# PX4uNode_V0_1_1.net
KiCad netlist of a schematic drawn in EAGLE
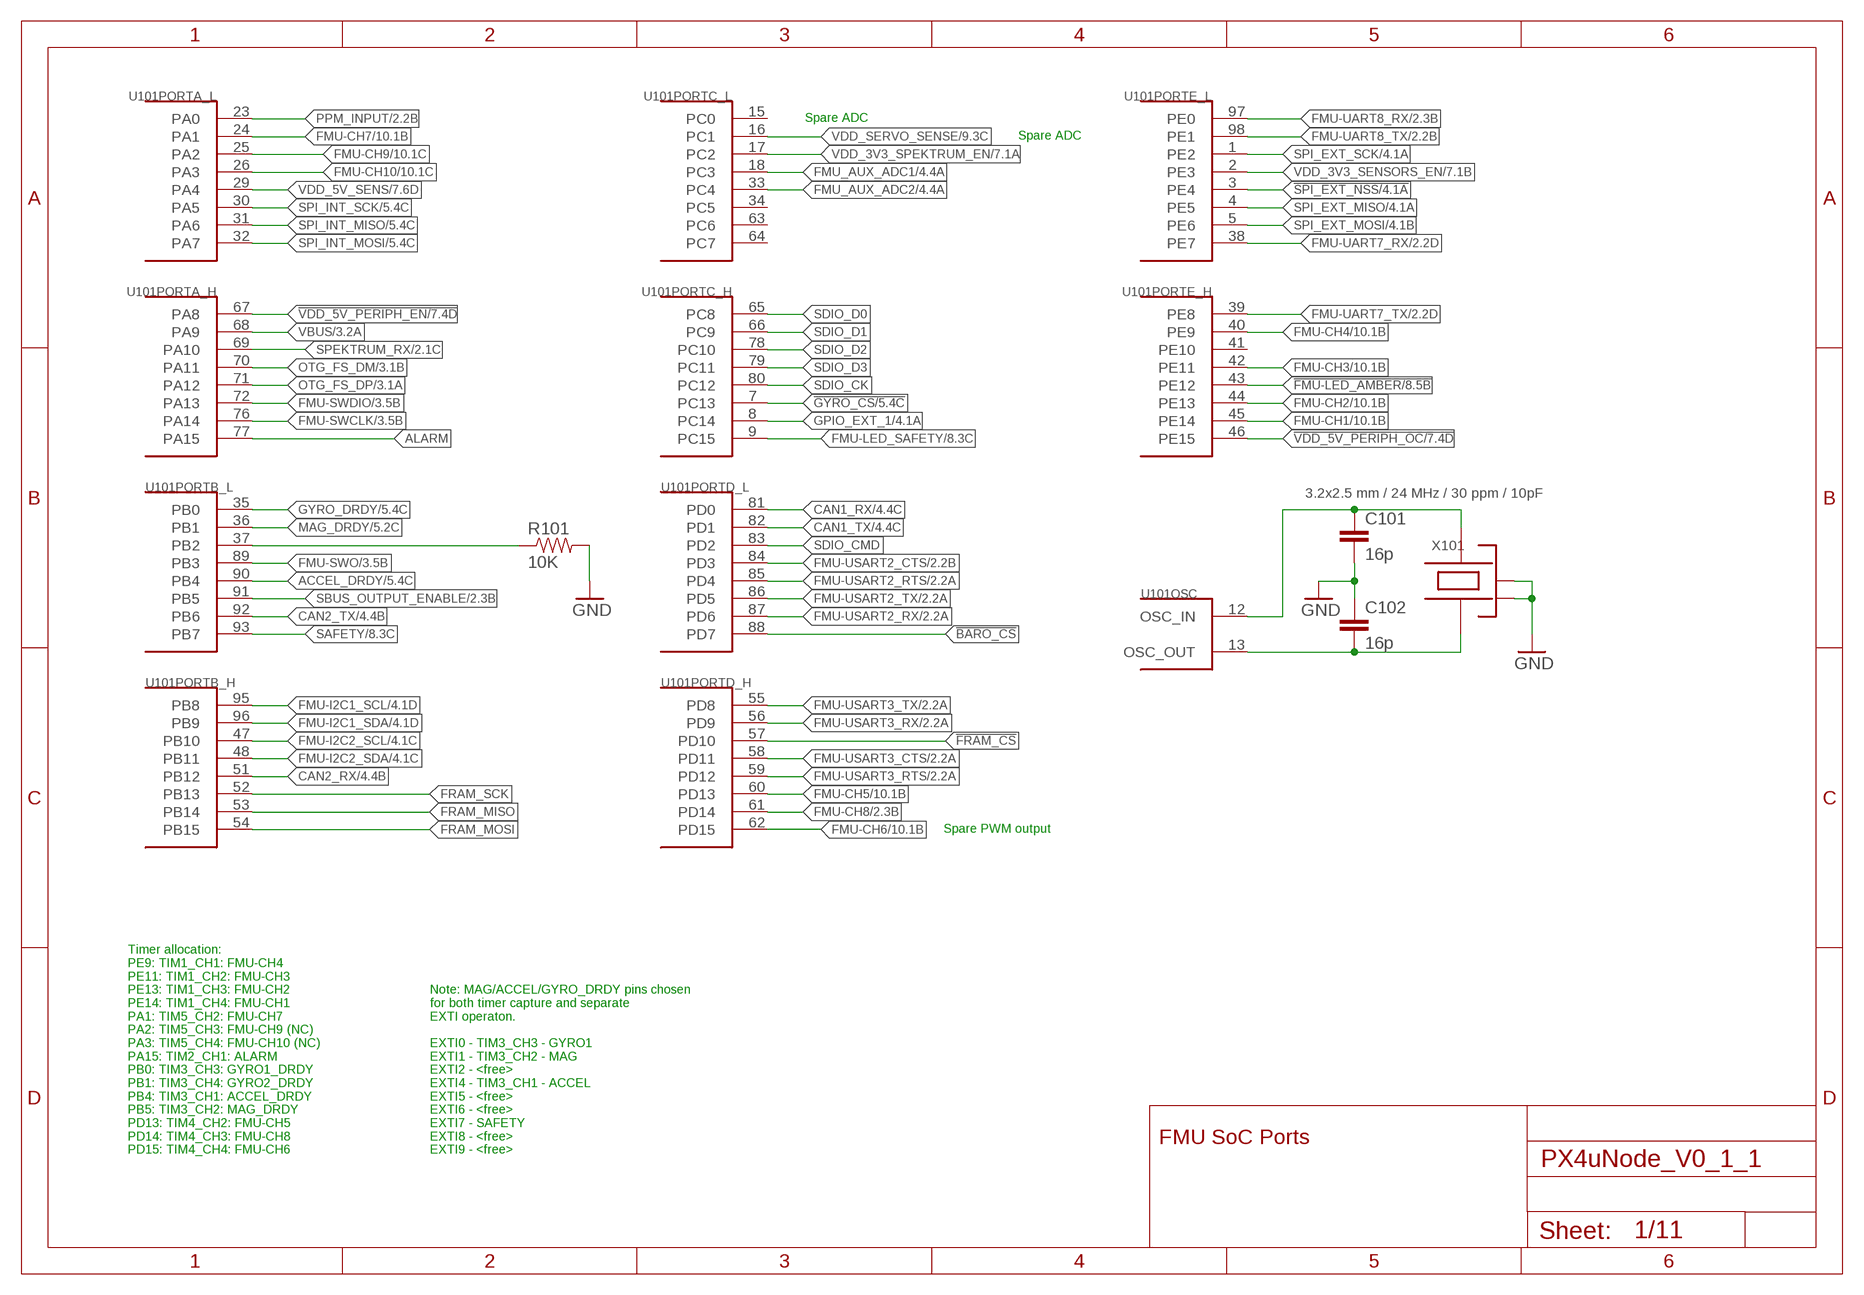
[diagram p0: schematic, sheet 1]
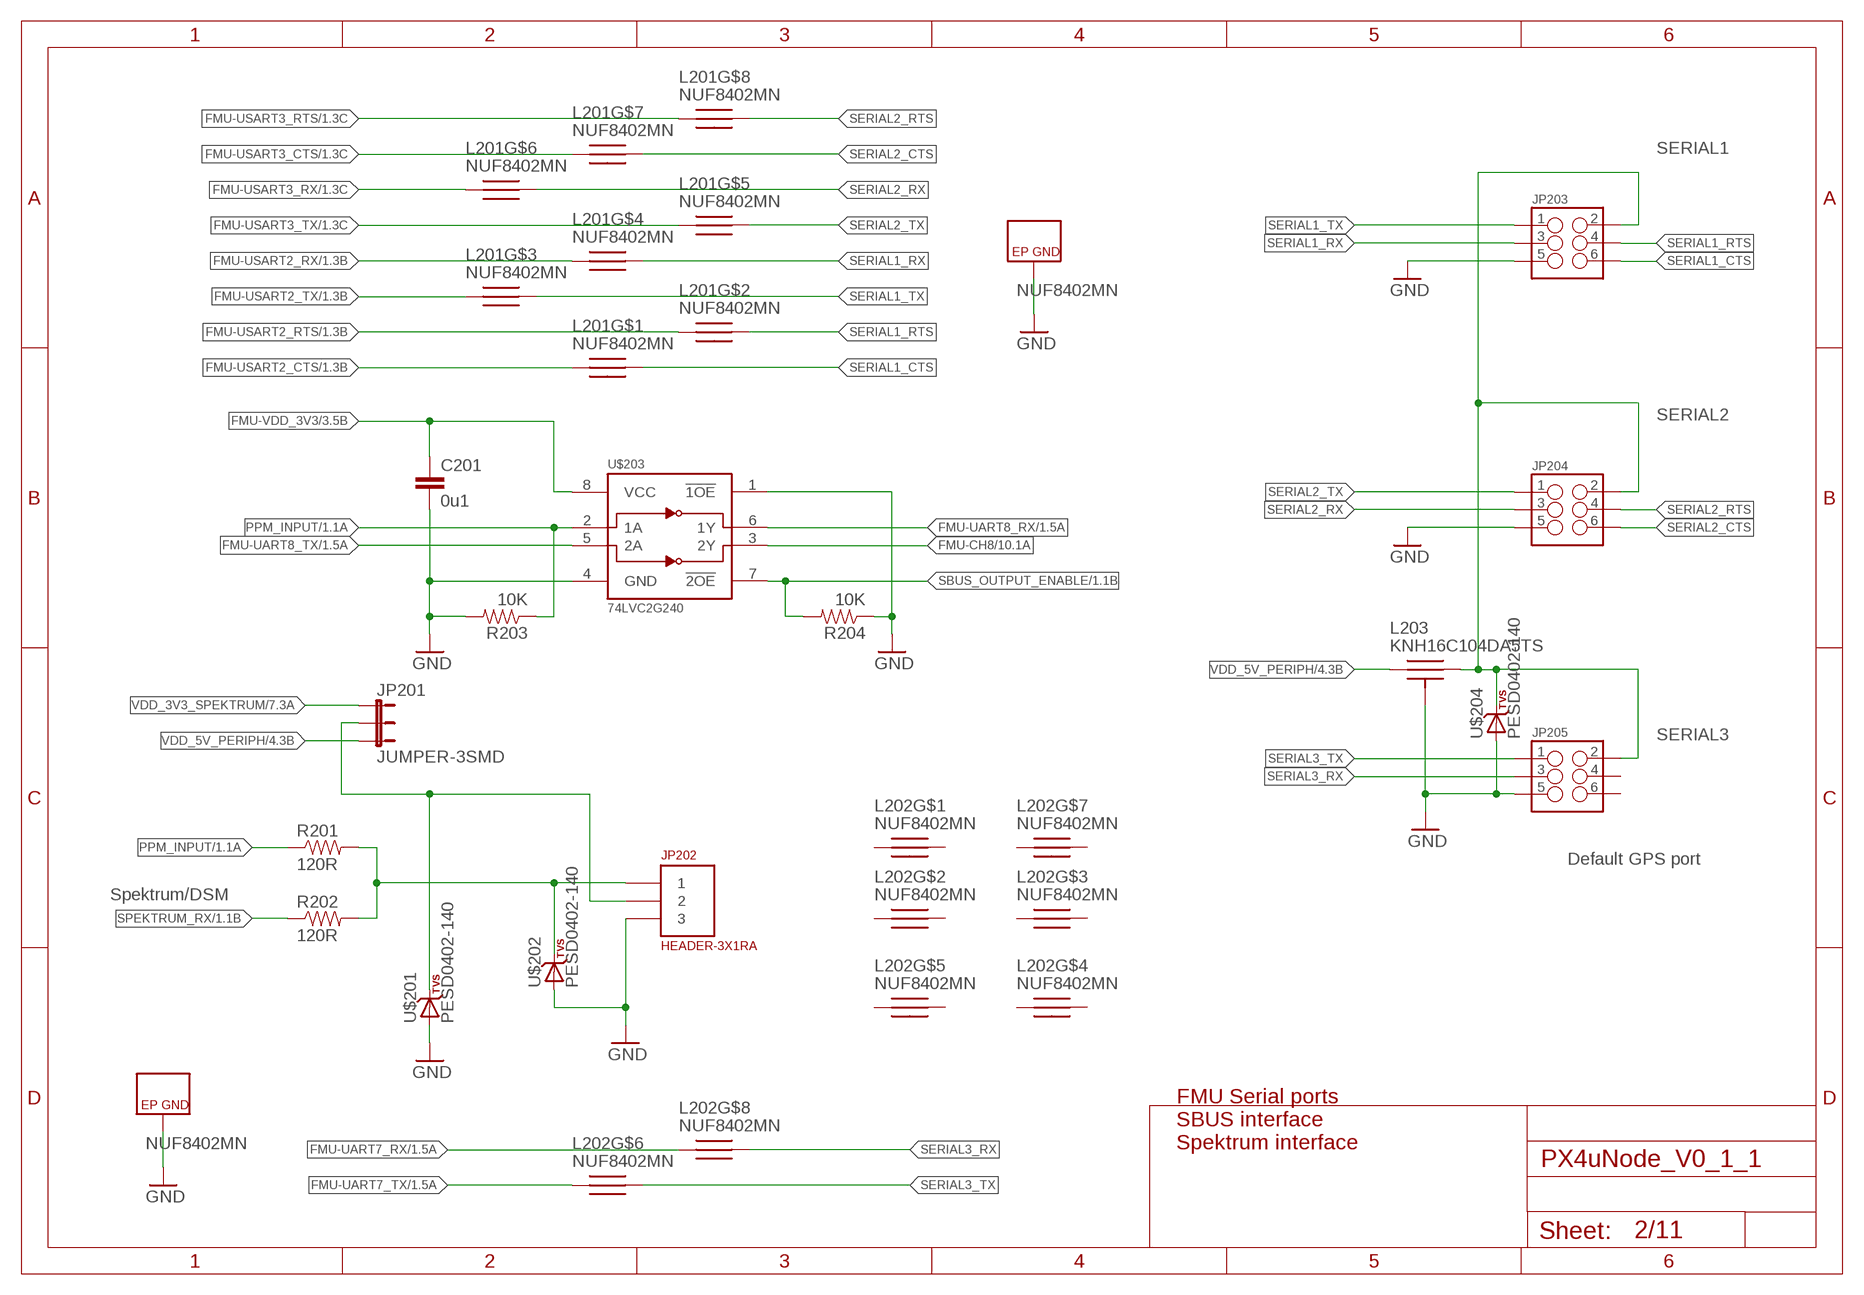
[diagram p1: schematic, sheet 2]
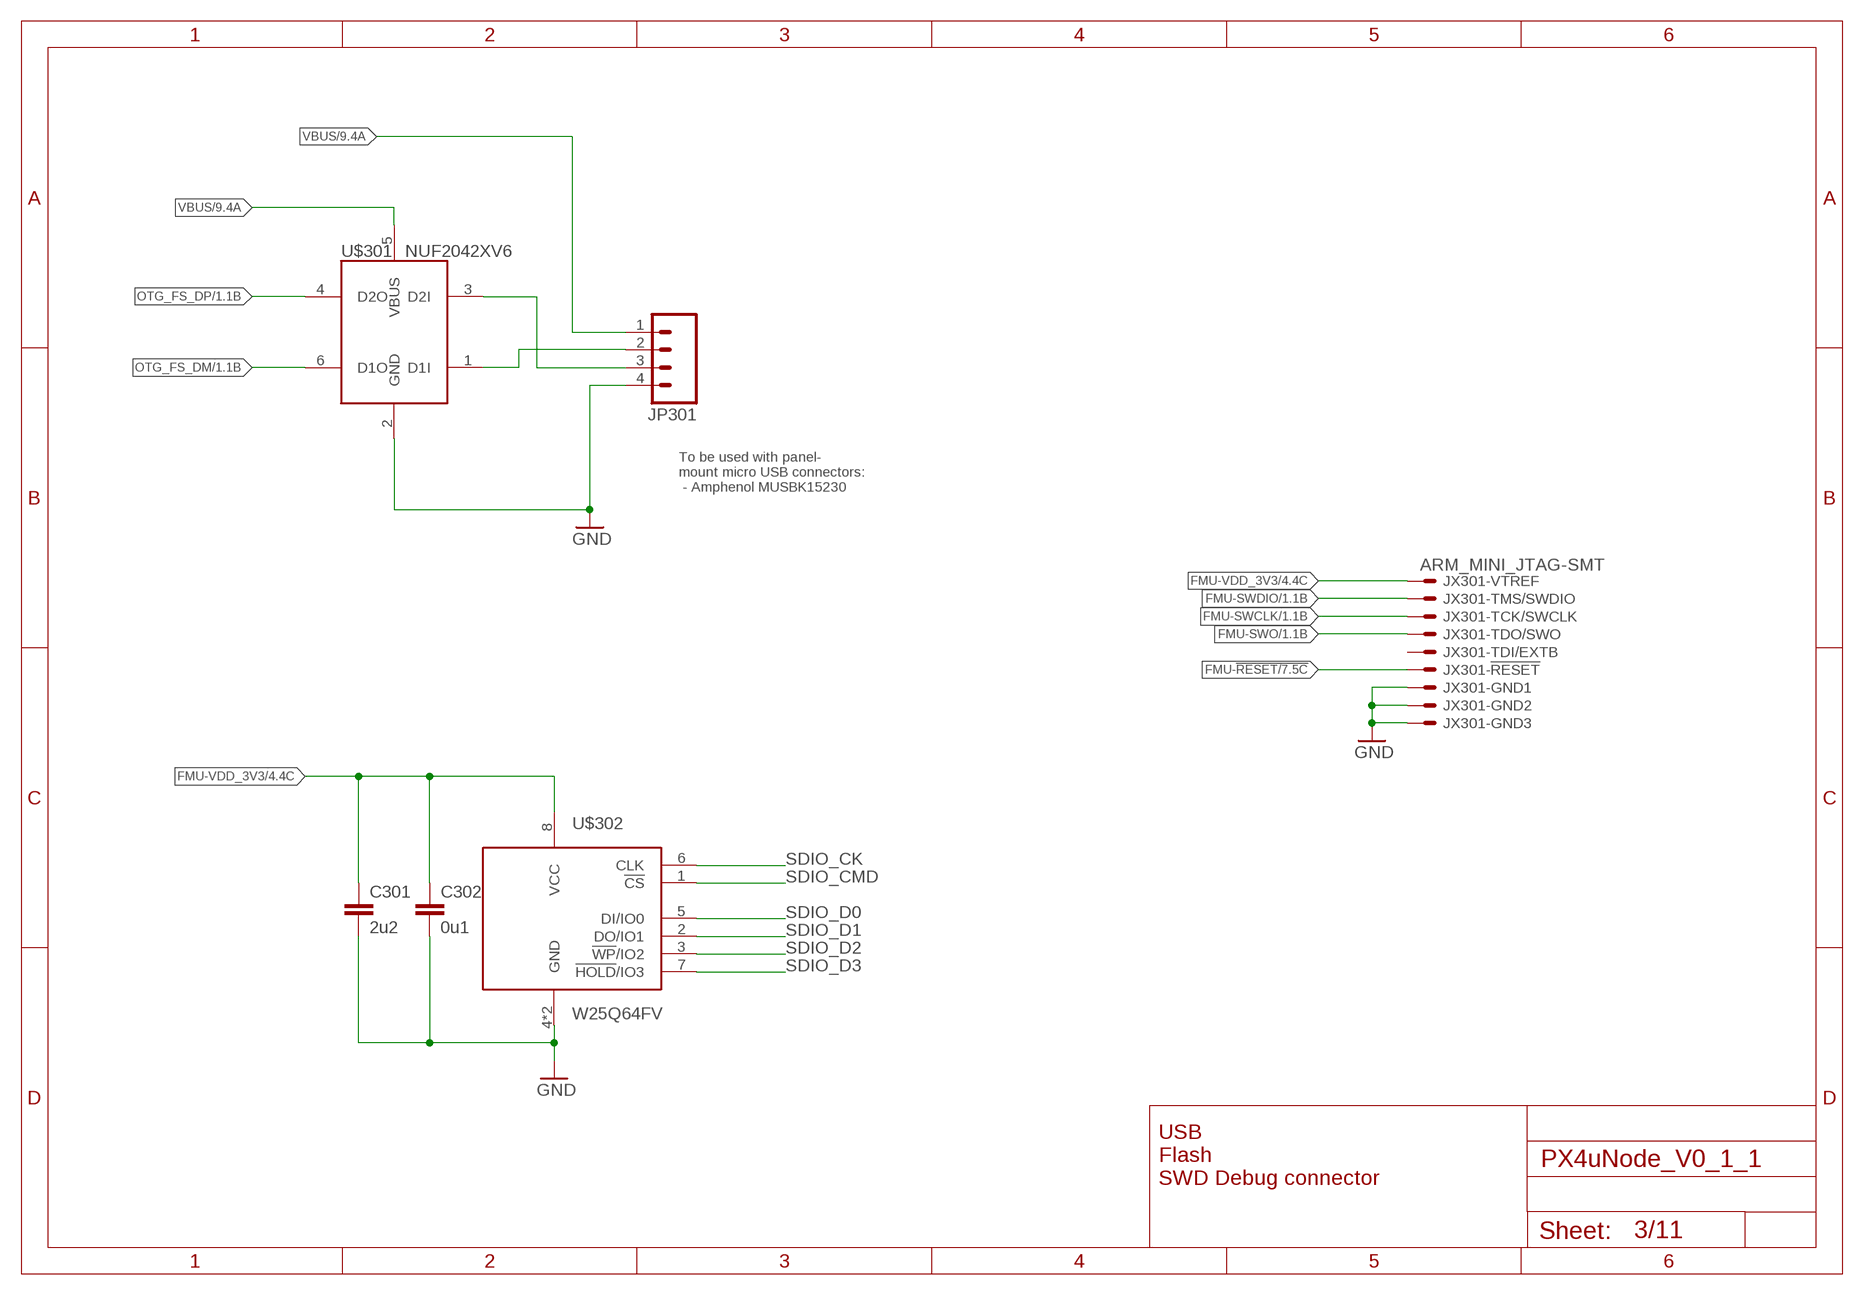
[diagram p2: schematic, sheet 3]
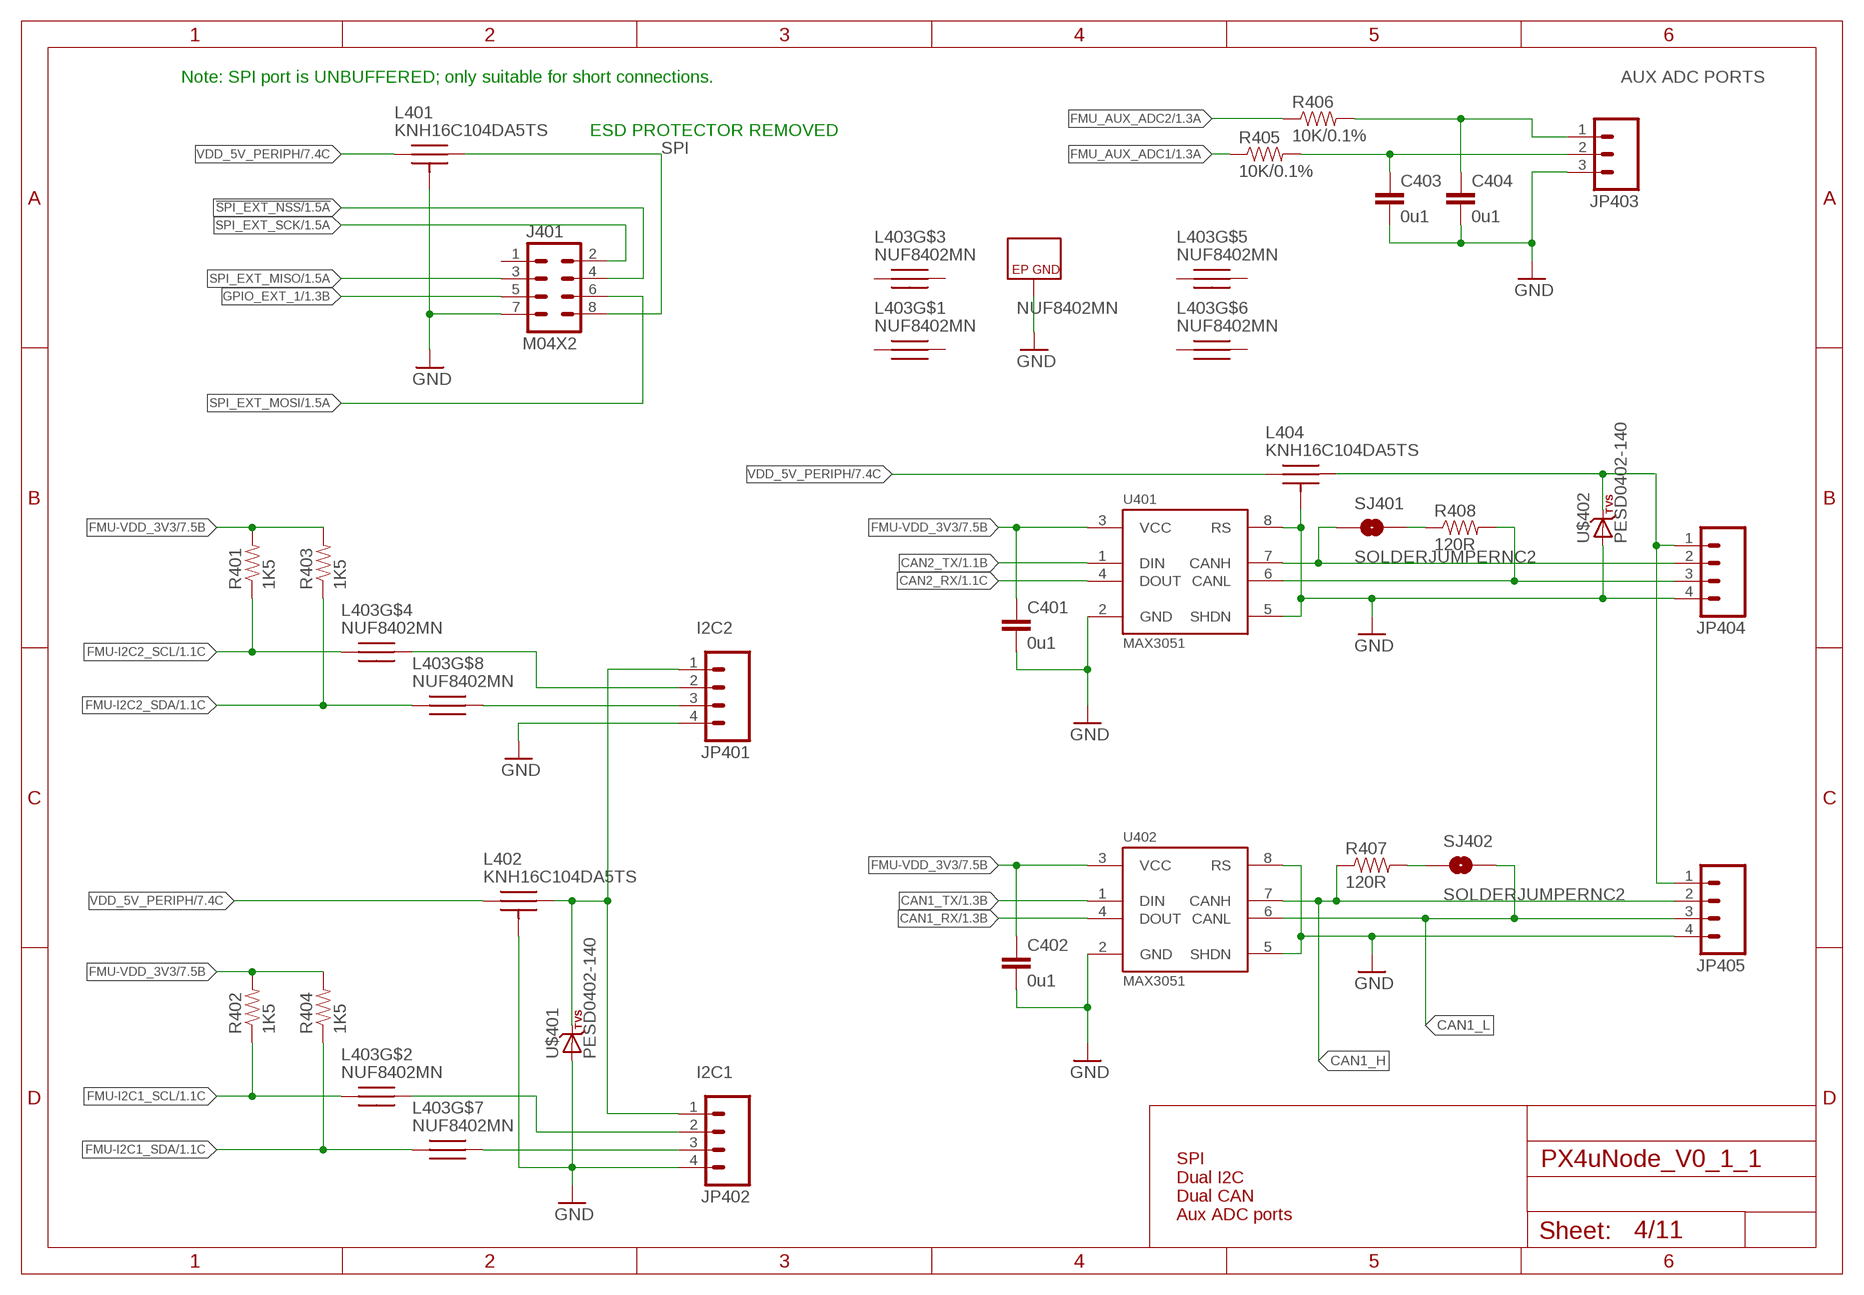
[diagram p3: schematic, sheet 4]
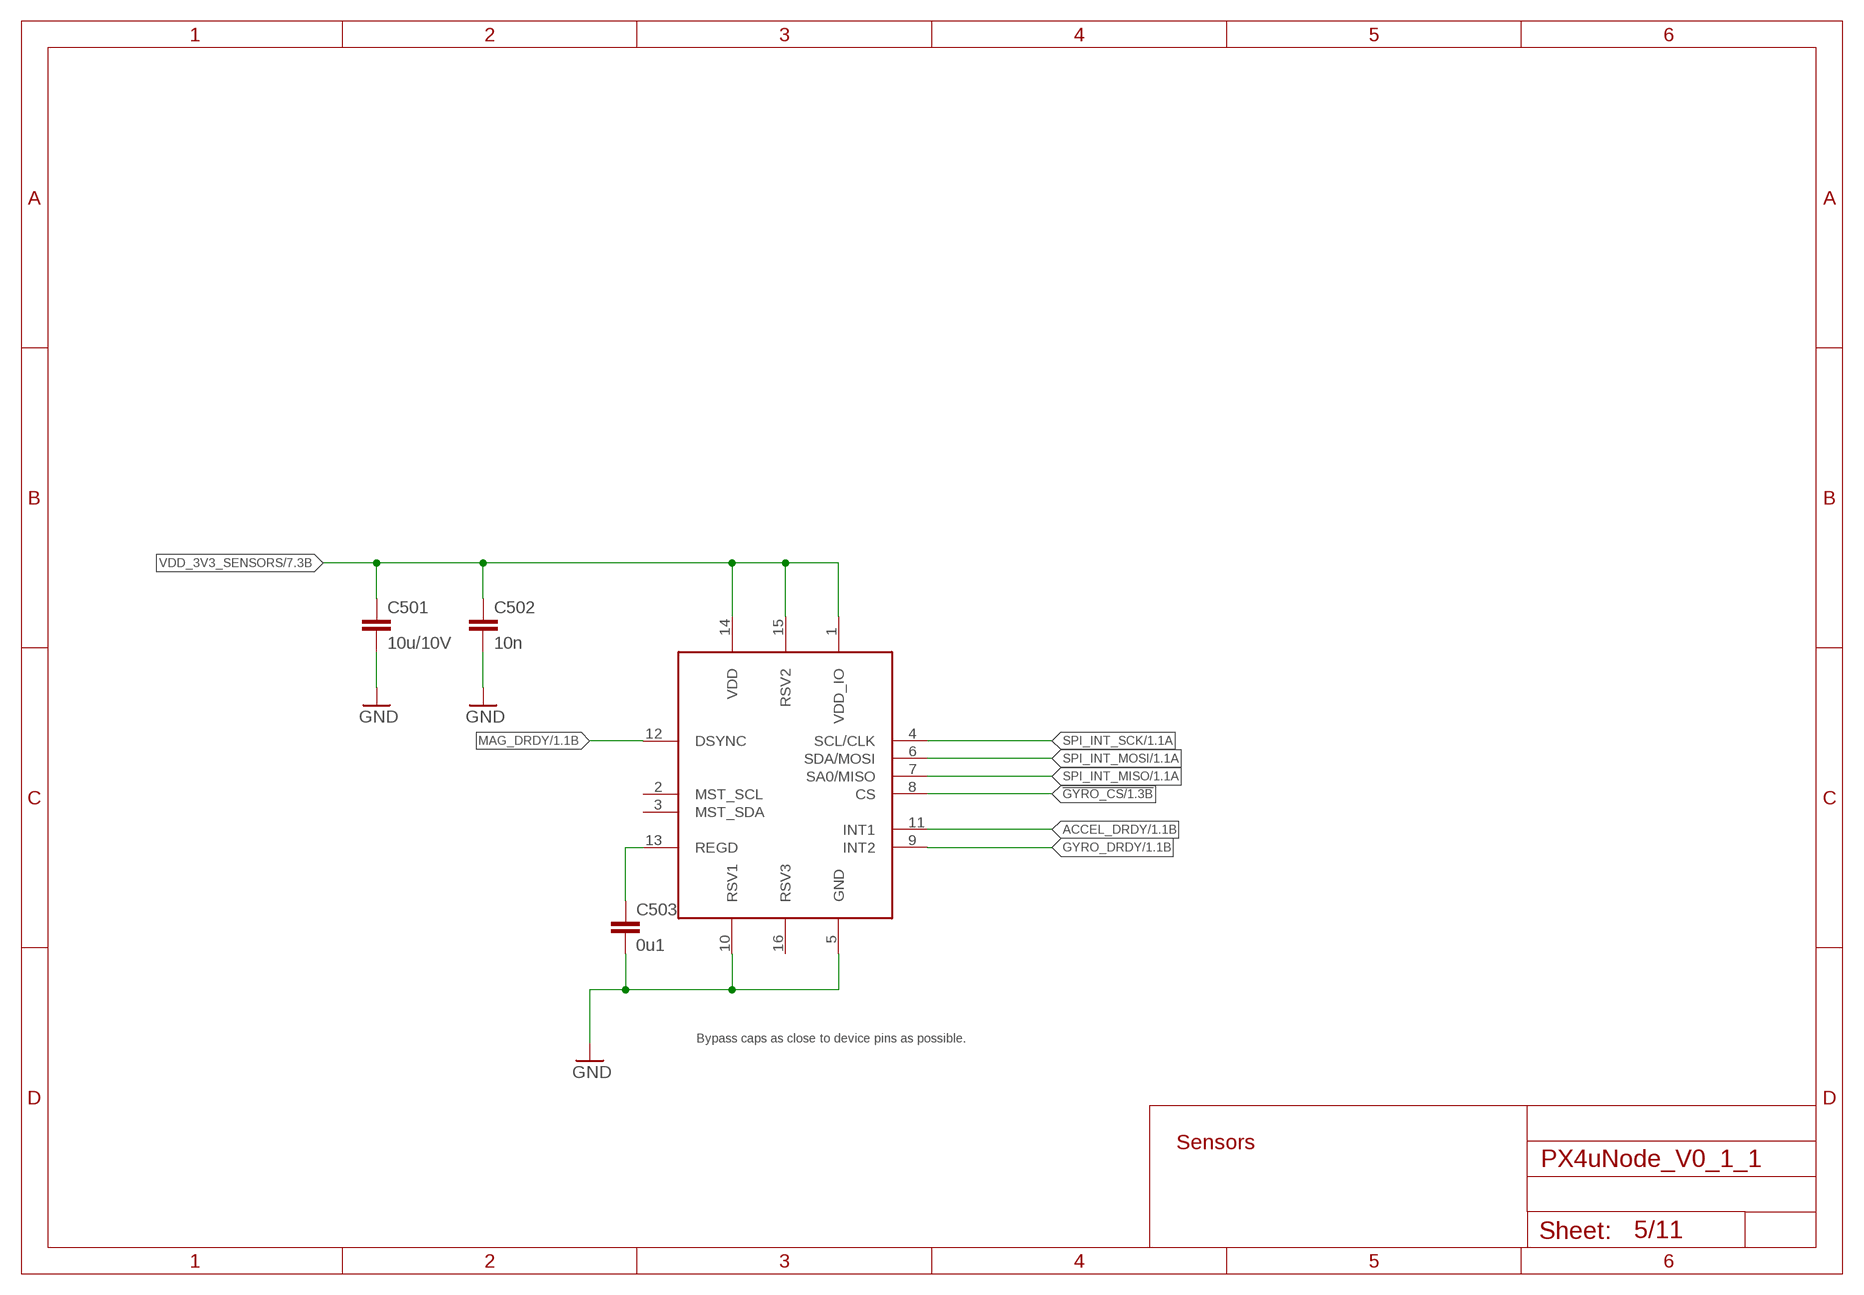
[diagram p4: schematic, sheet 5]
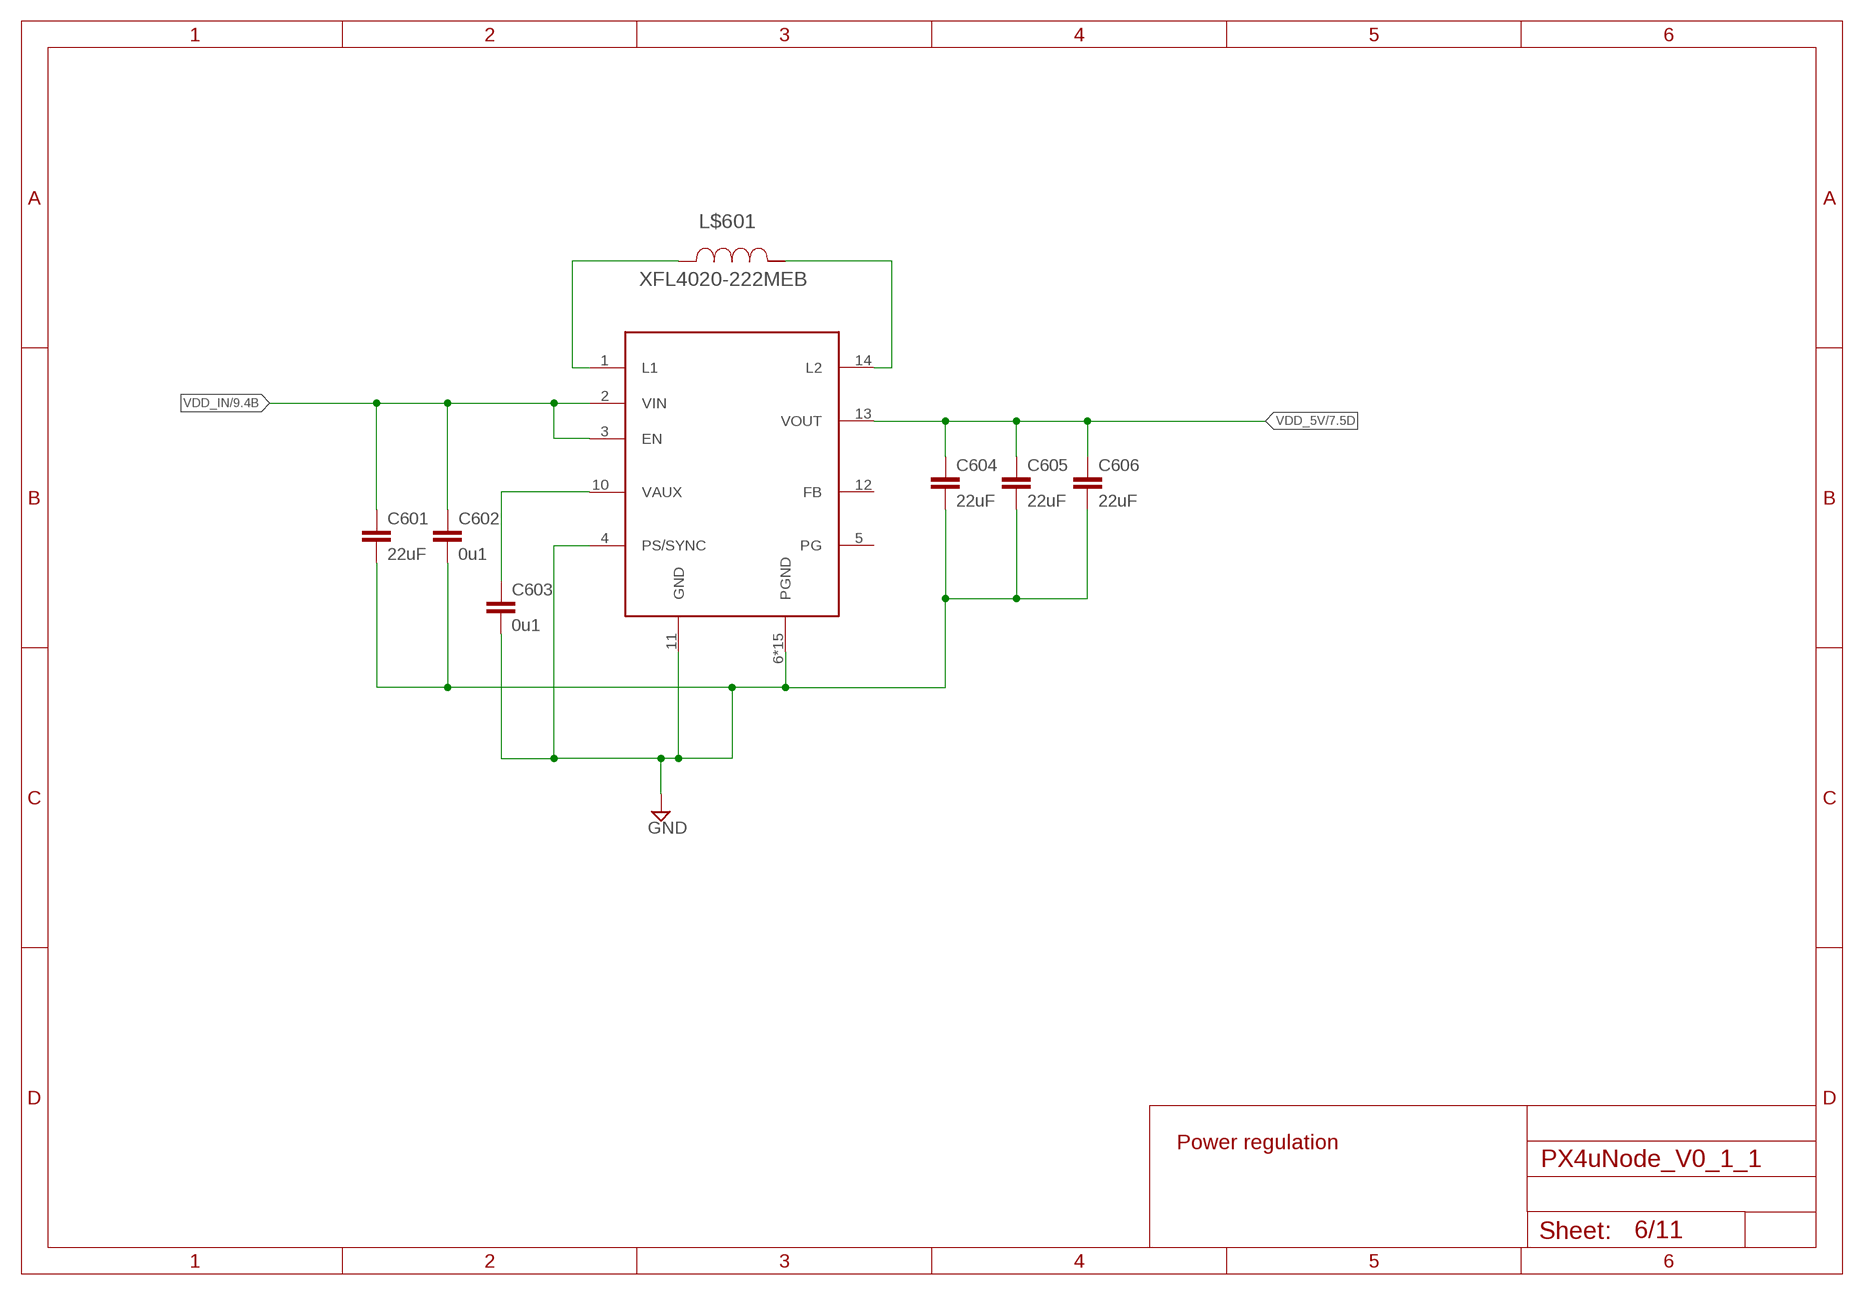
[diagram p5: schematic, sheet 6]
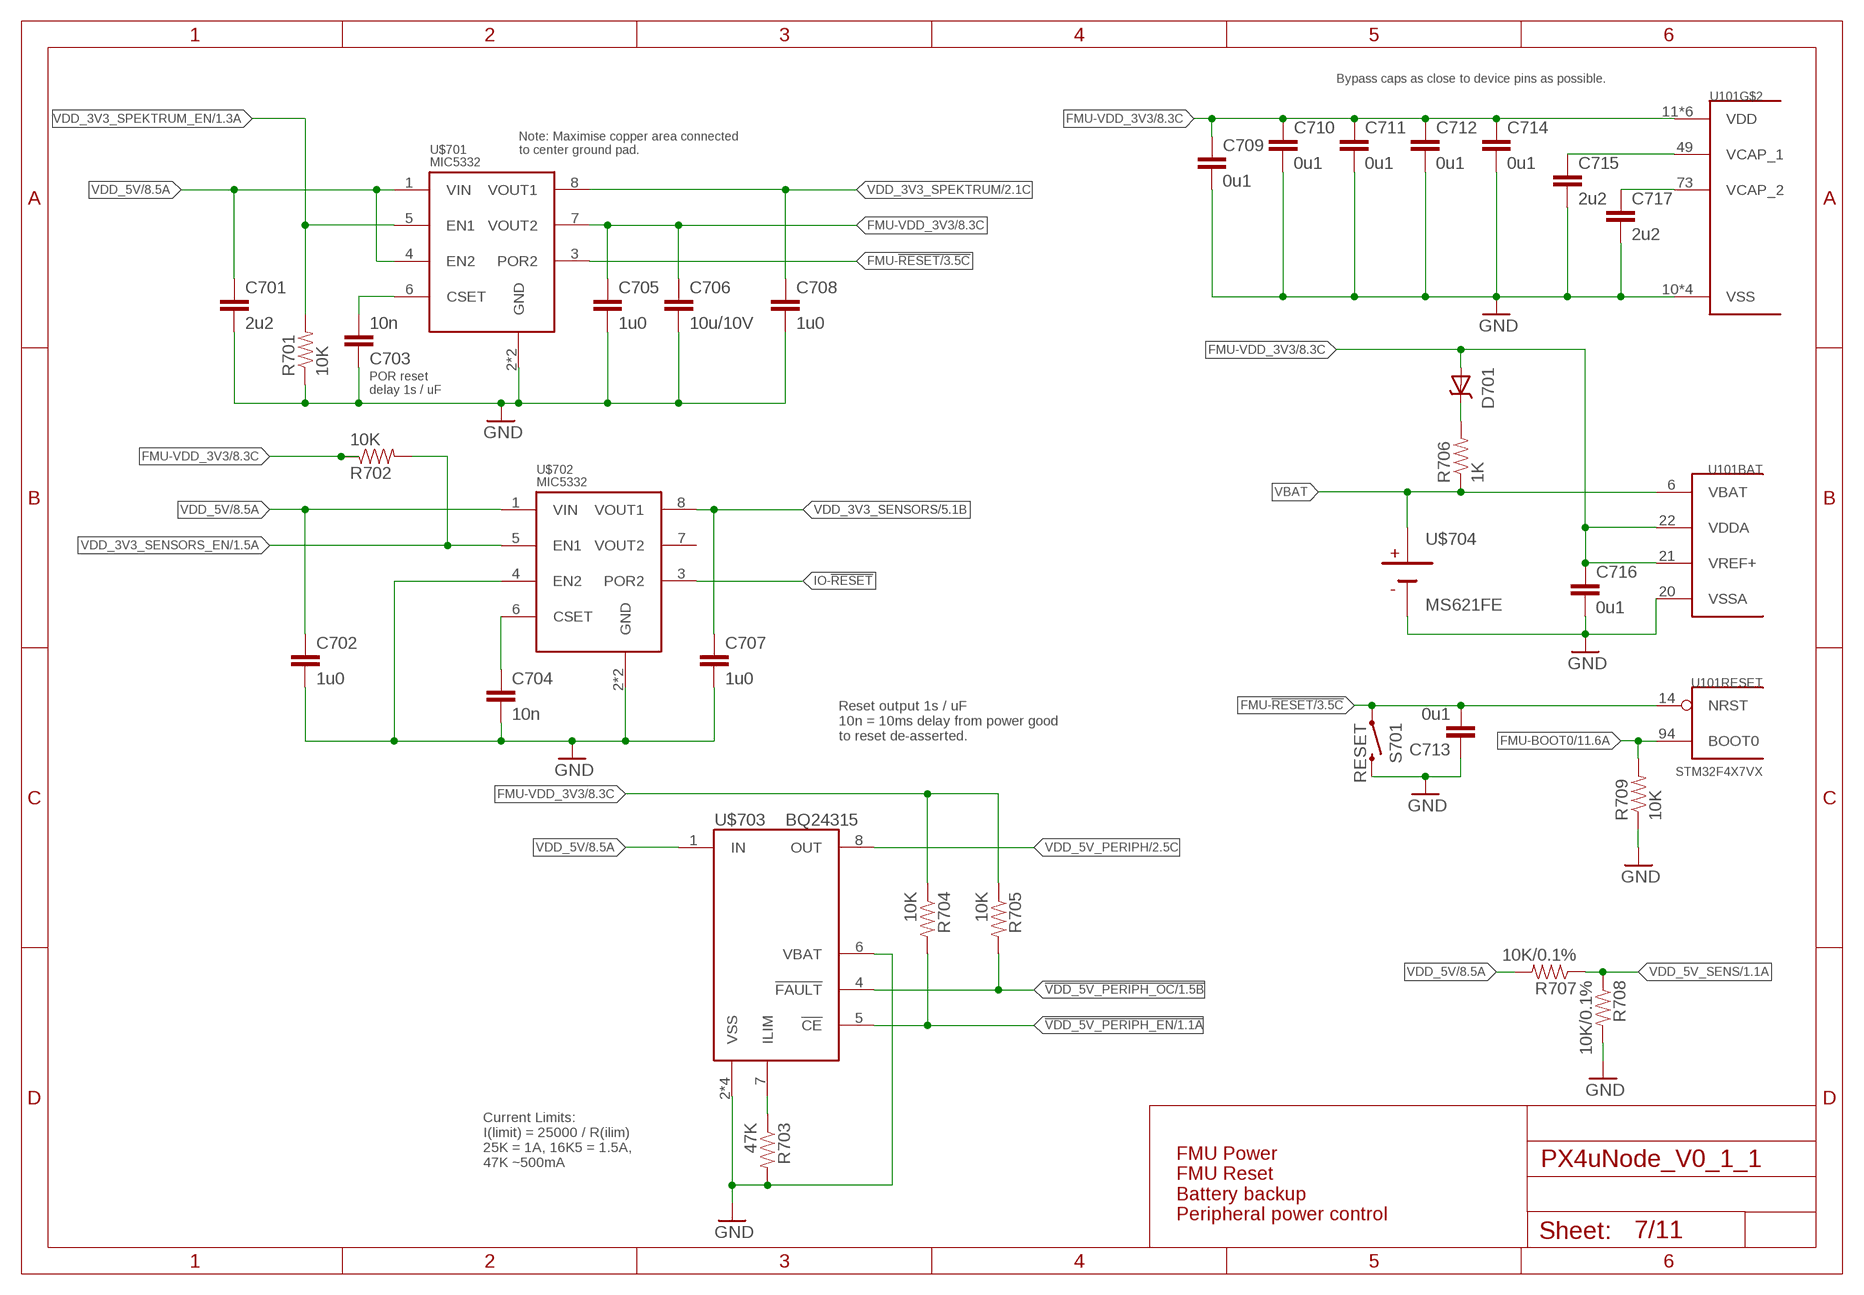
[diagram p6: schematic, sheet 7]
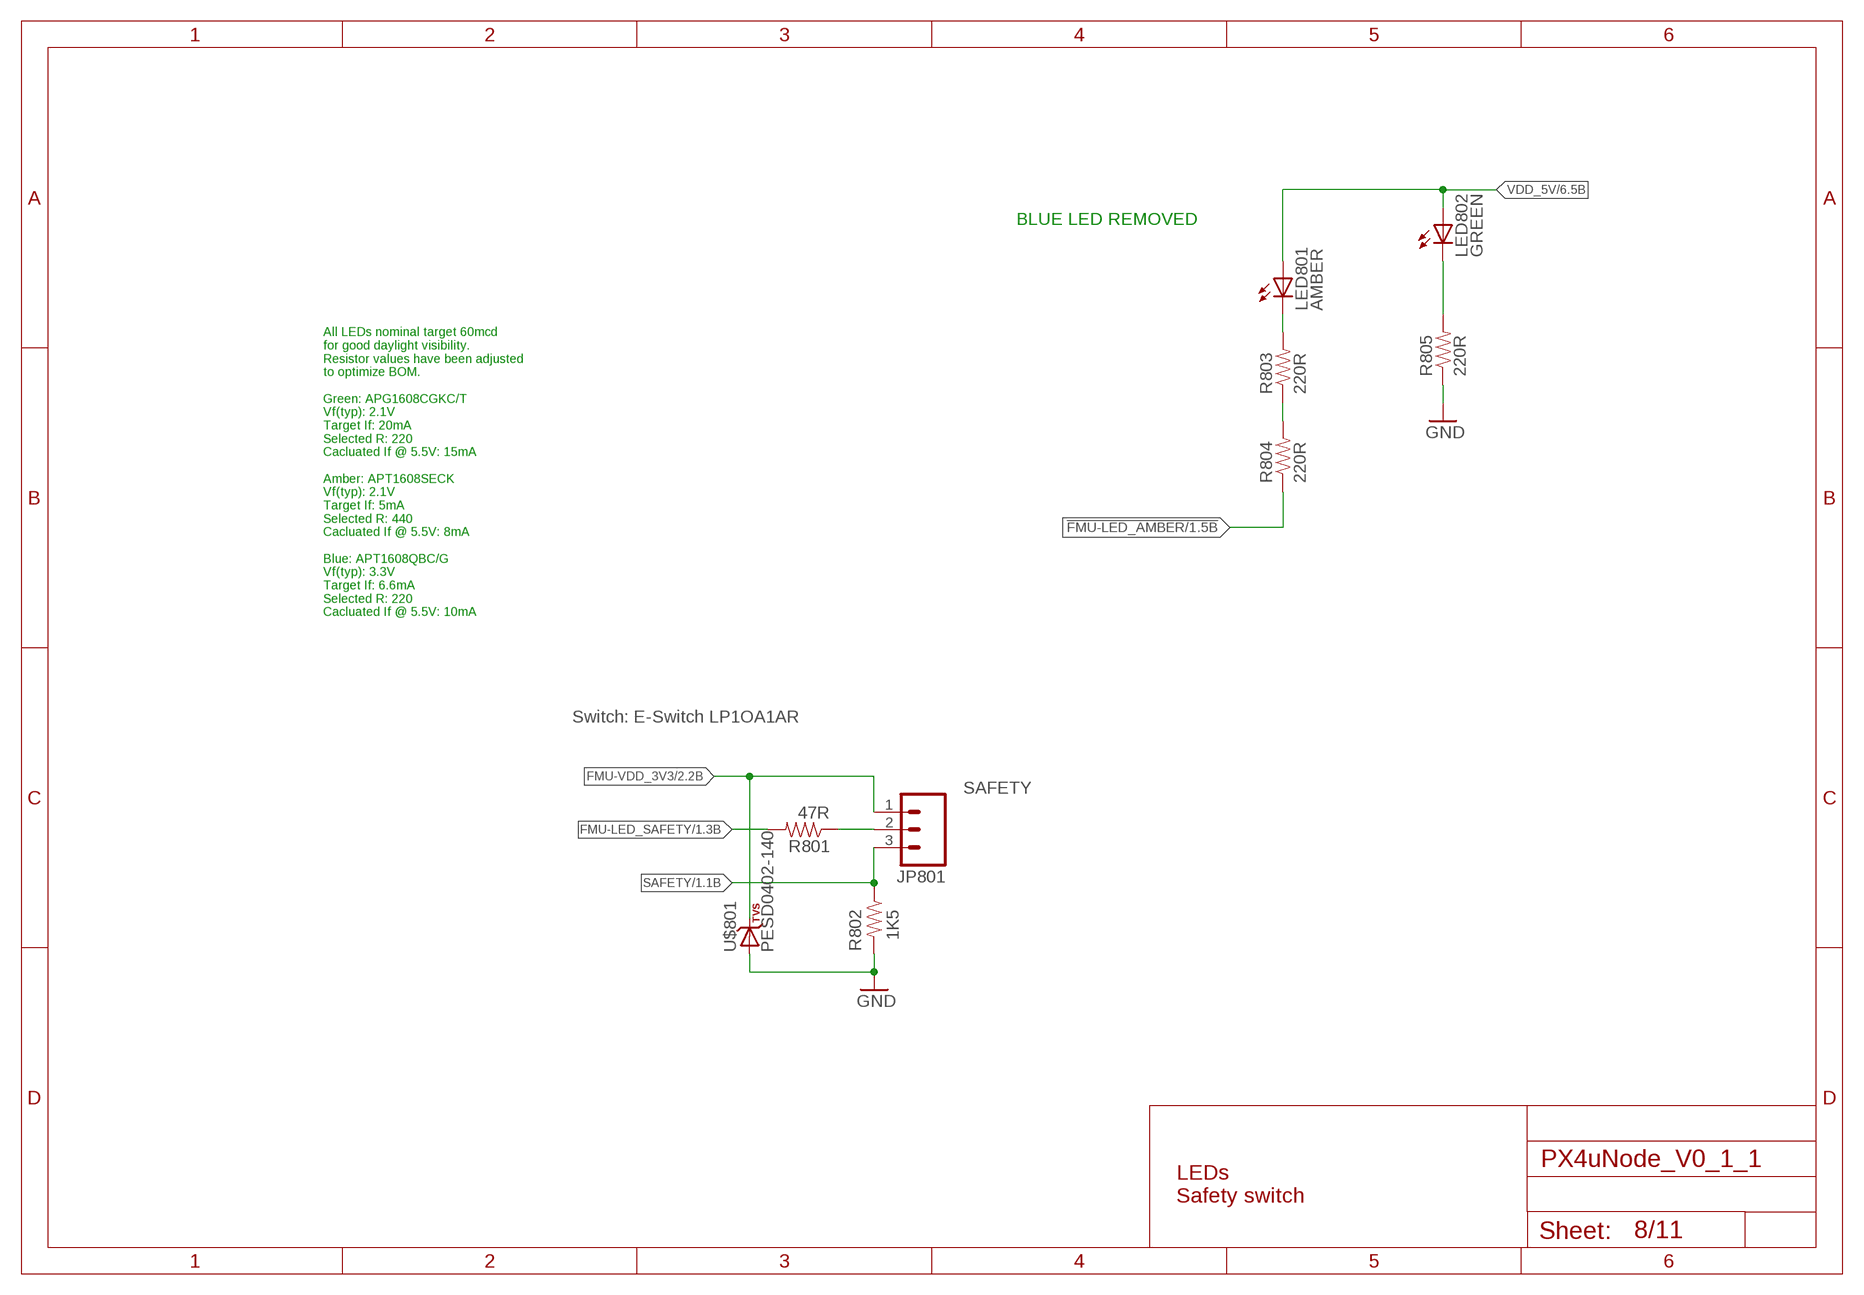
[diagram p7: schematic, sheet 8]
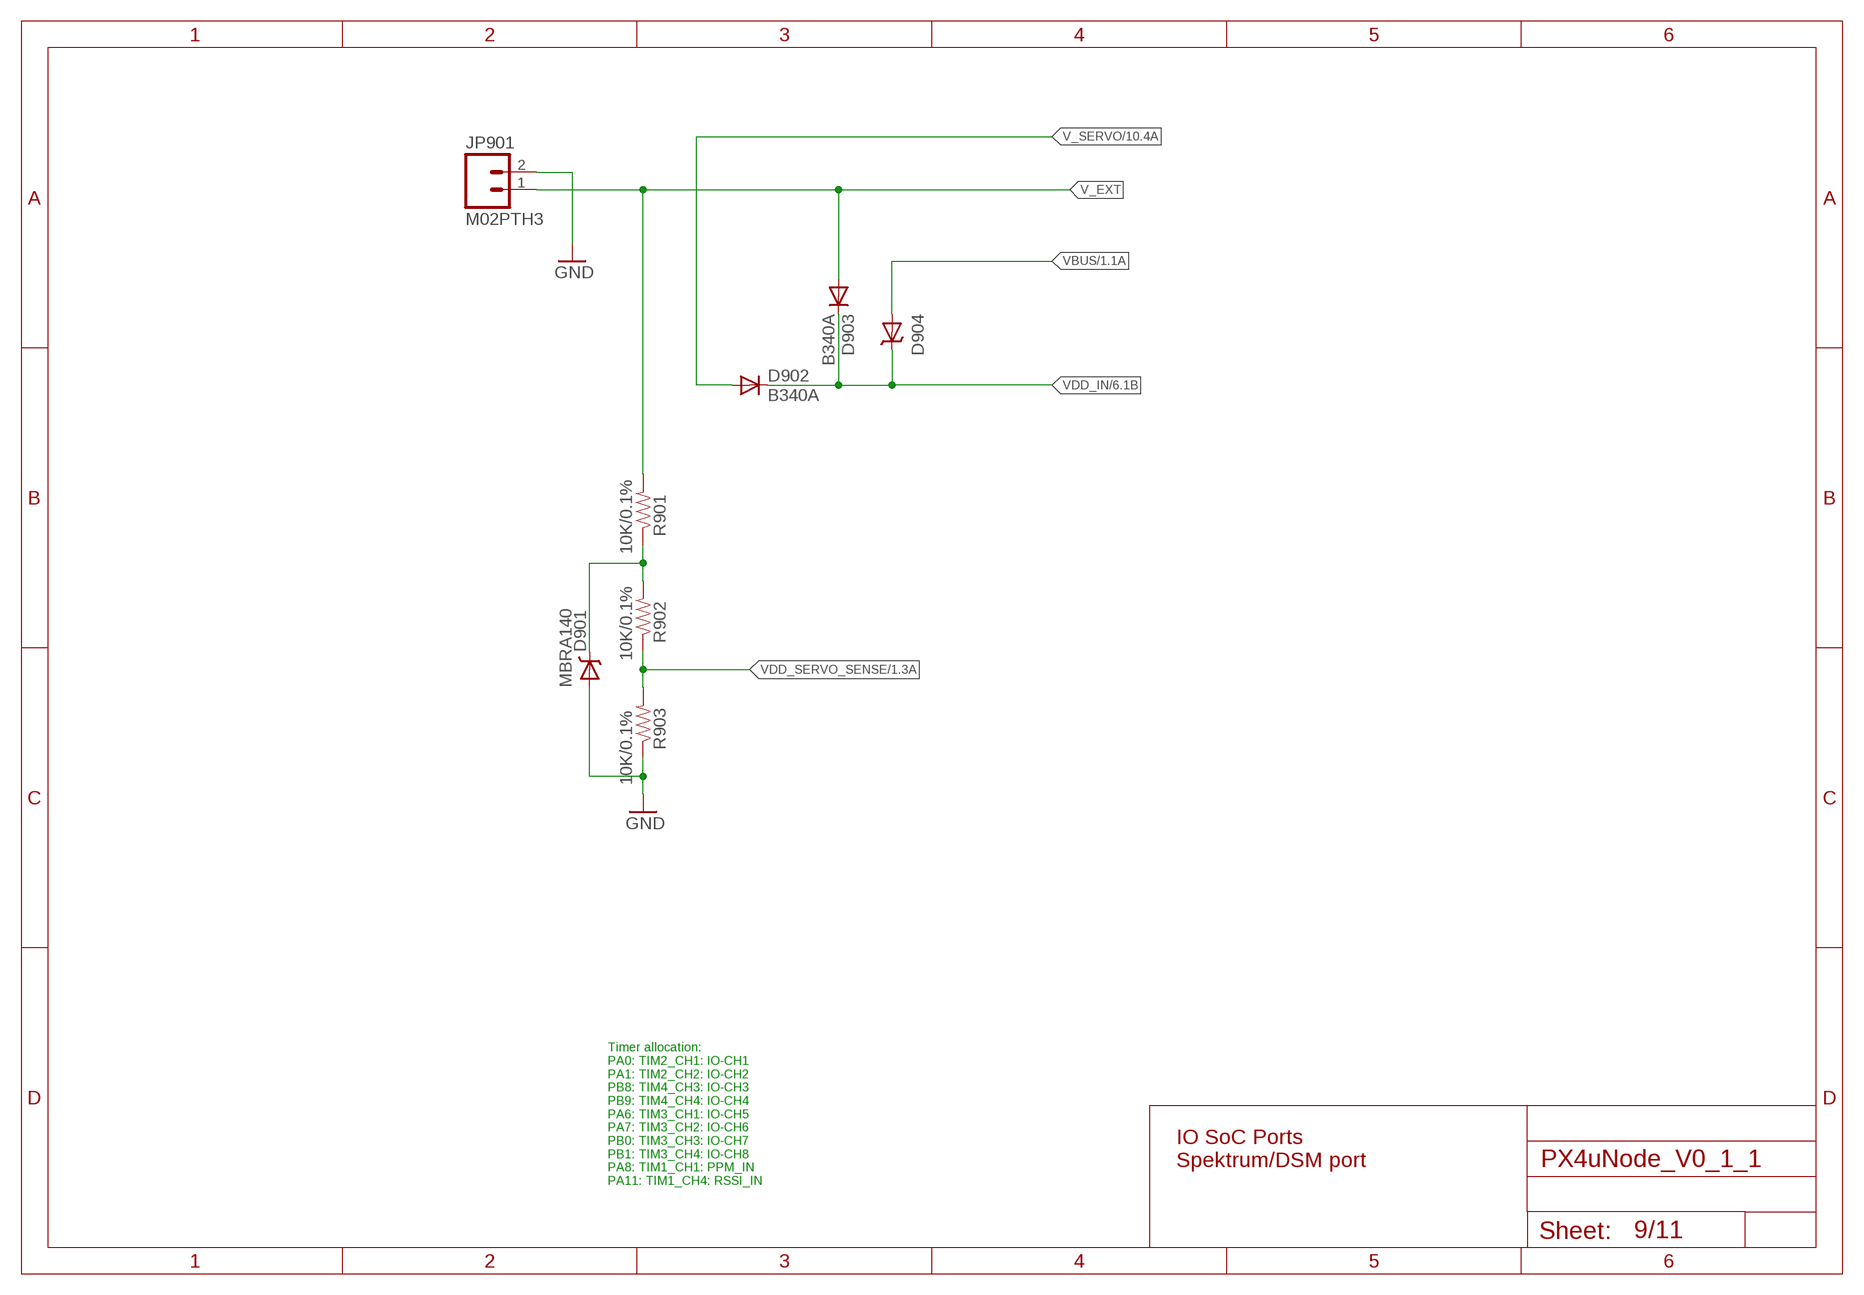
[diagram p8: schematic, sheet 9]
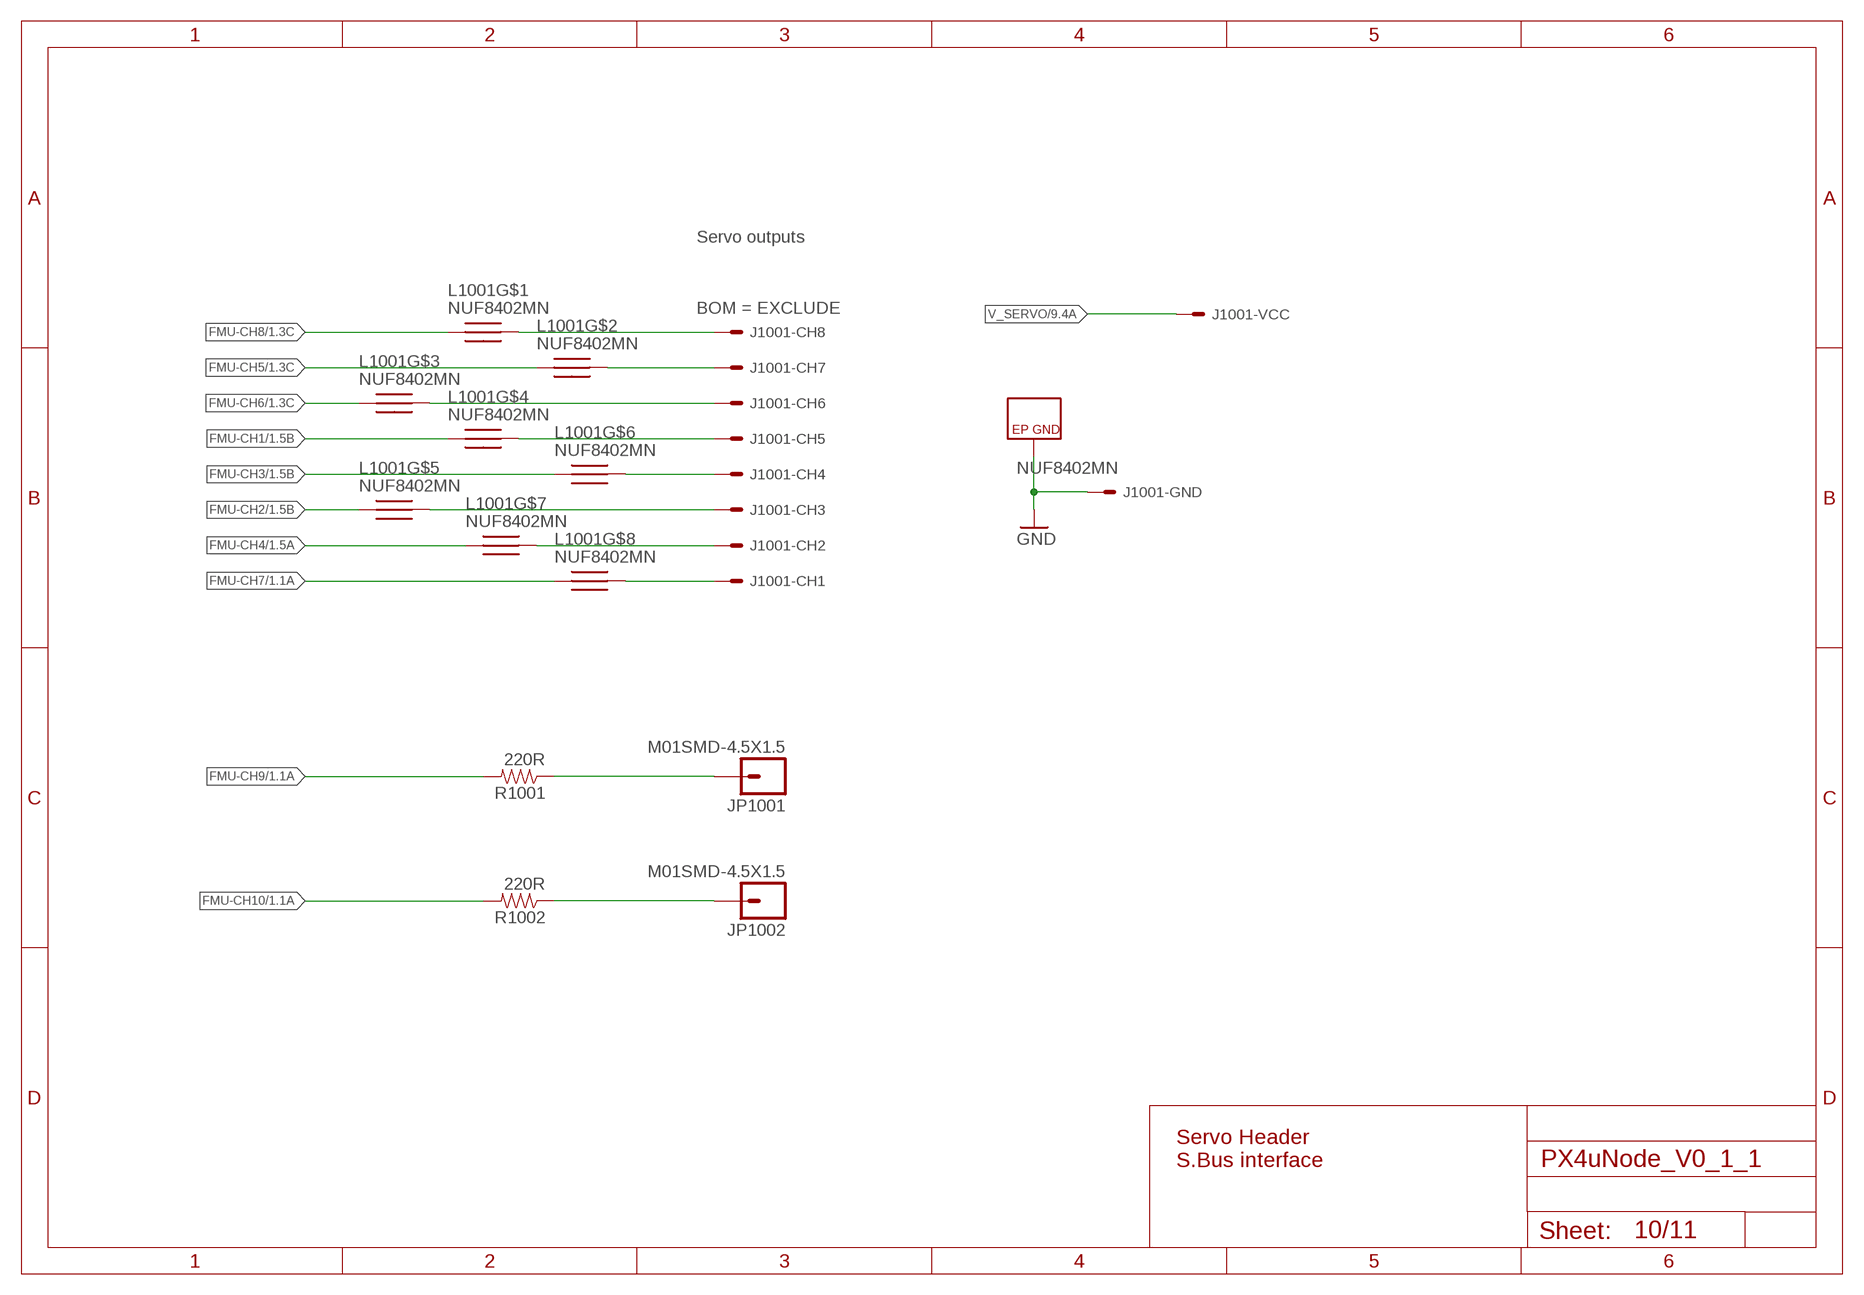
[diagram p9: schematic, sheet 10]
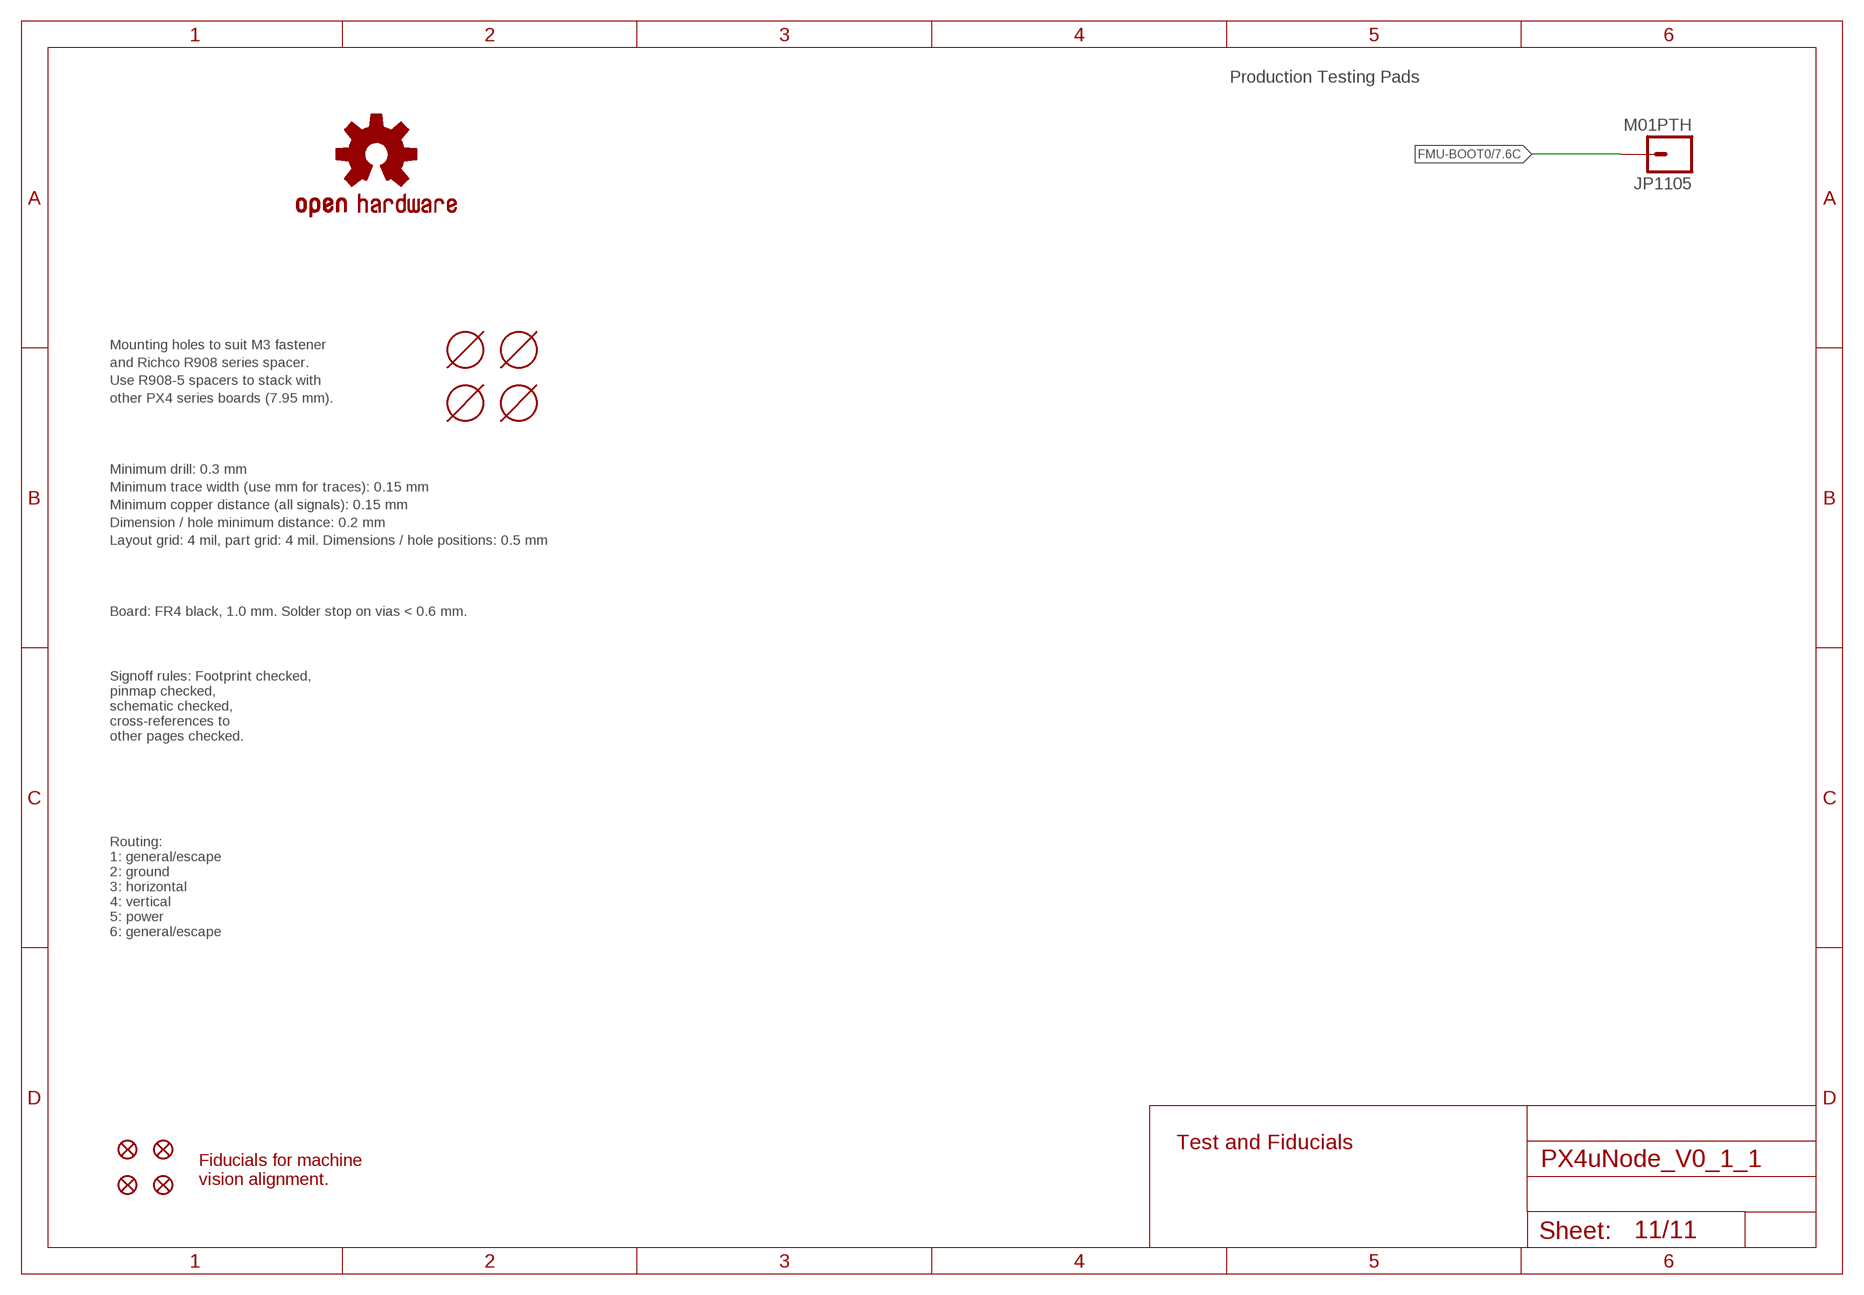
[diagram p10: schematic, sheet 11]

(export (version "E")
  (design (tool "Eeschema 10.0.6"))
  (components
    (comp (ref "C701")
      (value "2u2")
      (footprint "eagle-import:0603-CAP")
      (fields (field (name "PARTNO") "C1608Y5V1C225Z"))
      (libsource (lib "eagle-import") (part "CAP0603"))
    )
    (comp (ref "C702")
      (value "1u0")
      (footprint "eagle-import:0603-CAP")
      (fields (field (name "PARTNO") "CC0603ZRY5V7BB105"))
      (libsource (lib "eagle-import") (part "CAP0603"))
    )
    (comp (ref "C703")
      (value "10n")
      (footprint "eagle-import:0402-CAP")
      (fields (field (name "PARTNO") "CC0402KRX7R7BB103"))
      (libsource (lib "eagle-import") (part "CAP0402"))
    )
    (comp (ref "C704")
      (value "10n")
      (footprint "eagle-import:0402-CAP")
      (fields (field (name "PARTNO") "CC0402KRX7R7BB103"))
      (libsource (lib "eagle-import") (part "CAP0402"))
    )
    (comp (ref "C705")
      (value "1u0")
      (footprint "eagle-import:0603-CAP")
      (fields (field (name "PARTNO") "CC0603ZRY5V7BB105"))
      (libsource (lib "eagle-import") (part "CAP0603"))
    )
    (comp (ref "C706")
      (value "10u/10V")
      (footprint "eagle-import:0805-CAP")
      (fields (field (name "PARTNO") "CC0805ZKY5V6BB106"))
      (libsource (lib "eagle-import") (part "CAP0805"))
    )
    (comp (ref "C707")
      (value "1u0")
      (footprint "eagle-import:0603-CAP")
      (fields (field (name "PARTNO") "CC0603ZRY5V7BB105"))
      (libsource (lib "eagle-import") (part "CAP0603"))
    )
    (comp (ref "C708")
      (value "1u0")
      (footprint "eagle-import:0603-CAP")
      (fields (field (name "PARTNO") "CC0603ZRY5V7BB105"))
      (libsource (lib "eagle-import") (part "CAP0603"))
    )
    (comp (ref "C709")
      (value "0u1")
      (footprint "eagle-import:0402-CAP")
      (fields (field (name "PARTNO") "CC0402ZRY5V7BB104"))
      (libsource (lib "eagle-import") (part "CAP0402"))
    )
    (comp (ref "C710")
      (value "0u1")
      (footprint "eagle-import:0402-CAP")
      (fields (field (name "PARTNO") "CC0402ZRY5V7BB104"))
      (libsource (lib "eagle-import") (part "CAP0402"))
    )
    (comp (ref "C711")
      (value "0u1")
      (footprint "eagle-import:0402-CAP")
      (fields (field (name "PARTNO") "CC0402ZRY5V7BB104"))
      (libsource (lib "eagle-import") (part "CAP0402"))
    )
    (comp (ref "C712")
      (value "0u1")
      (footprint "eagle-import:0402-CAP")
      (fields (field (name "PARTNO") "CC0402ZRY5V7BB104"))
      (libsource (lib "eagle-import") (part "CAP0402"))
    )
    (comp (ref "C713")
      (value "0u1")
      (footprint "eagle-import:0402-CAP")
      (fields (field (name "PARTNO") "CC0402ZRY5V7BB104"))
      (libsource (lib "eagle-import") (part "CAP0402"))
    )
    (comp (ref "C714")
      (value "0u1")
      (footprint "eagle-import:0402-CAP")
      (fields (field (name "PARTNO") "CC0402ZRY5V7BB104"))
      (libsource (lib "eagle-import") (part "CAP0402"))
    )
    (comp (ref "C715")
      (value "2u2")
      (footprint "eagle-import:0603-CAP")
      (fields (field (name "PARTNO") "C1608Y5V1C225Z"))
      (libsource (lib "eagle-import") (part "CAP0603"))
    )
    (comp (ref "C716")
      (value "0u1")
      (footprint "eagle-import:0402-CAP")
      (fields (field (name "PARTNO") "CC0402ZRY5V7BB104"))
      (libsource (lib "eagle-import") (part "CAP0402"))
    )
    (comp (ref "C717")
      (value "2u2")
      (footprint "eagle-import:0603-CAP")
      (fields (field (name "PARTNO") "C1608Y5V1C225Z"))
      (libsource (lib "eagle-import") (part "CAP0603"))
    )
    (comp (ref "D701")
      (value "DIODE-SCHOTTKY")
      (footprint "eagle-import:SOD-523")
      (fields (field (name "PARTNO") "MBRA140"))
      (libsource (lib "eagle-import") (part "DIODE-SCHOTTKY"))
    )
    (comp (ref "R701")
      (value "10K")
      (footprint "eagle-import:0402-RES")
      (fields (field (name "PARTNO") "RC0402FR-0710KL"))
      (libsource (lib "eagle-import") (part "RESISTOR0402-RES"))
    )
    (comp (ref "R702")
      (value "10K")
      (footprint "eagle-import:0402-RES")
      (fields (field (name "PARTNO") "RC0402FR-0710KL"))
      (libsource (lib "eagle-import") (part "RESISTOR0402-RES"))
    )
    (comp (ref "R703")
      (value "47K")
      (footprint "eagle-import:0402-RES")
      (fields (field (name "PARTNO") "RMCF0402FT47K"))
      (libsource (lib "eagle-import") (part "RESISTOR0402-RES"))
    )
    (comp (ref "R704")
      (value "10K")
      (footprint "eagle-import:0402-RES")
      (fields (field (name "PARTNO") "RC0402FR-0710KL"))
      (libsource (lib "eagle-import") (part "RESISTOR0402-RES"))
    )
    (comp (ref "R705")
      (value "10K")
      (footprint "eagle-import:0402-RES")
      (fields (field (name "PARTNO") "RC0402FR-0710KL"))
      (libsource (lib "eagle-import") (part "RESISTOR0402-RES"))
    )
    (comp (ref "R706")
      (value "1K")
      (footprint "eagle-import:0402-RES")
      (fields (field (name "PARTNO") "RC0402FR-071KL"))
      (libsource (lib "eagle-import") (part "RESISTOR0402-RES"))
    )
    (comp (ref "R707")
      (value "10K/0.1%")
      (footprint "eagle-import:0402-RES")
      (fields (field (name "PARTNO") "ERA-2AEB103X"))
      (libsource (lib "eagle-import") (part "RESISTOR0402-RES"))
    )
    (comp (ref "R708")
      (value "10K/0.1%")
      (footprint "eagle-import:0402-RES")
      (fields (field (name "PARTNO") "ERA-2AEB103X"))
      (libsource (lib "eagle-import") (part "RESISTOR0402-RES"))
    )
    (comp (ref "R709")
      (value "10K")
      (footprint "eagle-import:0402-RES")
      (fields (field (name "PARTNO") "RC0402FR-0710KL"))
      (libsource (lib "eagle-import") (part "RESISTOR0402-RES"))
    )
    (comp (ref "S701")
      (value "RESET")
      (footprint "eagle-import:EVQP7J01K")
      (fields (field (name "PARTNO") "EVQP7J01K"))
      (libsource (lib "eagle-import") (part "SWITCH-MOMENTARY-2"))
    )
    (comp (ref "U$701")
      (value "MIC5332")
      (footprint "eagle-import:MLF-8-EPAD")
      (fields (field (name "PARTNO") "MIC5332-SSYMT"))
      (libsource (lib "eagle-import") (part "MIC5332"))
    )
    (comp (ref "U$702")
      (value "MIC5332")
      (footprint "eagle-import:MLF-8-EPAD")
      (fields (field (name "PARTNO") "MIC5332-SSYMT"))
      (libsource (lib "eagle-import") (part "MIC5332"))
    )
    (comp (ref "U$703")
      (value "BQ24315")
      (footprint "eagle-import:QFN8-DSG")
      (fields (field (name "PARTNO") "BQ24315DSGR"))
      (libsource (lib "eagle-import") (part "BQ24315"))
    )
    (comp (ref "U$704")
      (value "MS621FE")
      (footprint "eagle-import:MS621FE")
      (libsource (lib "eagle-import") (part "MS621FE"))
    )
    (comp (ref "U101")
      (value "STM32F4X7VX")
      (footprint "eagle-import:TQFP100")
      (fields (field (name "PARTNO") "STM32F427VI"))
      (libsource (lib "eagle-import") (part "STM32F4X7VX"))
    )
    (comp (ref "D901")
      (value "DIODE-SCHOTTKY")
      (footprint "eagle-import:SOD-523")
      (fields (field (name "PARTNO") "MBRA140"))
      (libsource (lib "eagle-import") (part "DIODE-SCHOTTKY"))
    )
    (comp (ref "D902")
      (value "B340A")
      (footprint "eagle-import:SMA-DIODE")
      (libsource (lib "eagle-import") (part "DIODESMA"))
    )
    (comp (ref "D903")
      (value "B340A")
      (footprint "eagle-import:SMA-DIODE")
      (libsource (lib "eagle-import") (part "DIODESMA"))
    )
    (comp (ref "D904")
      (value "MSS1P4-M3")
      (footprint "eagle-import:MICROSMP")
      (fields (field (name "PARTNO") "MSS1P4-M3/89A"))
      (libsource (lib "eagle-import") (part "DIODE-SCHOTTKY_MSMP"))
    )
    (comp (ref "JP901")
      (value "M02PTH3")
      (footprint "eagle-import:1X02_LONGPADS")
      (libsource (lib "eagle-import") (part "M02PTH3"))
    )
    (comp (ref "R901")
      (value "10K/0.1%")
      (footprint "eagle-import:0402-RES")
      (fields (field (name "PARTNO") "ERA-2AEB103X"))
      (libsource (lib "eagle-import") (part "RESISTOR0402-RES"))
    )
    (comp (ref "R902")
      (value "10K/0.1%")
      (footprint "eagle-import:0402-RES")
      (fields (field (name "PARTNO") "ERA-2AEB103X"))
      (libsource (lib "eagle-import") (part "RESISTOR0402-RES"))
    )
    (comp (ref "R903")
      (value "10K/0.1%")
      (footprint "eagle-import:0402-RES")
      (fields (field (name "PARTNO") "ERA-2AEB103X"))
      (libsource (lib "eagle-import") (part "RESISTOR0402-RES"))
    )
    (comp (ref "C401")
      (value "0u1")
      (footprint "eagle-import:0402-CAP")
      (fields (field (name "PARTNO") "CC0402ZRY5V7BB104"))
      (libsource (lib "eagle-import") (part "CAP0402"))
    )
    (comp (ref "C402")
      (value "0u1")
      (footprint "eagle-import:0402-CAP")
      (fields (field (name "PARTNO") "CC0402ZRY5V7BB104"))
      (libsource (lib "eagle-import") (part "CAP0402"))
    )
    (comp (ref "C403")
      (value "0u1")
      (footprint "eagle-import:0402-CAP")
      (fields (field (name "PARTNO") "CC0402ZRY5V7BB104"))
      (libsource (lib "eagle-import") (part "CAP0402"))
    )
    (comp (ref "C404")
      (value "0u1")
      (footprint "eagle-import:0402-CAP")
      (fields (field (name "PARTNO") "CC0402ZRY5V7BB104"))
      (libsource (lib "eagle-import") (part "CAP0402"))
    )
    (comp (ref "J401")
      (value "M04X2")
      (footprint "eagle-import:2X4")
      (libsource (lib "eagle-import") (part "M04X2"))
    )
    (comp (ref "JP401")
      (value "M04PTH")
      (footprint "eagle-import:1X04")
      (libsource (lib "eagle-import") (part "M04PTH"))
    )
    (comp (ref "JP402")
      (value "M04PTH")
      (footprint "eagle-import:1X04")
      (libsource (lib "eagle-import") (part "M04PTH"))
    )
    (comp (ref "JP403")
      (value "M03PTH")
      (footprint "eagle-import:1X03")
      (fields (field (name "PARTNO") "EXCLUDE"))
      (libsource (lib "eagle-import") (part "M03PTH"))
    )
    (comp (ref "JP404")
      (value "M04PTH")
      (footprint "eagle-import:1X04")
      (libsource (lib "eagle-import") (part "M04PTH"))
    )
    (comp (ref "JP405")
      (value "M04PTH")
      (footprint "eagle-import:1X04")
      (libsource (lib "eagle-import") (part "M04PTH"))
    )
    (comp (ref "L401")
      (value "KNH16C104DA5TS")
      (footprint "eagle-import:KYOCERA-KNH16-DA")
      (libsource (lib "eagle-import") (part "KNH16C104DA5TS"))
    )
    (comp (ref "L402")
      (value "KNH16C104DA5TS")
      (footprint "eagle-import:KYOCERA-KNH16-DA")
      (libsource (lib "eagle-import") (part "KNH16C104DA5TS"))
    )
    (comp (ref "L403")
      (value "NUF8402MN")
      (footprint "eagle-import:DFN16-THIN")
      (fields (field (name "PARTNO") "NUF8402MN"))
      (libsource (lib "eagle-import") (part "NUF8402MN"))
    )
    (comp (ref "L404")
      (value "KNH16C104DA5TS")
      (footprint "eagle-import:KYOCERA-KNH16-DA")
      (libsource (lib "eagle-import") (part "KNH16C104DA5TS"))
    )
    (comp (ref "R401")
      (value "1K5")
      (footprint "eagle-import:0402-RES")
      (fields (field (name "PARTNO") "RC0402FR-071K5L"))
      (libsource (lib "eagle-import") (part "RESISTOR0402-RES"))
    )
    (comp (ref "R402")
      (value "1K5")
      (footprint "eagle-import:0402-RES")
      (fields (field (name "PARTNO") "RC0402FR-071K5L"))
      (libsource (lib "eagle-import") (part "RESISTOR0402-RES"))
    )
    (comp (ref "R403")
      (value "1K5")
      (footprint "eagle-import:0402-RES")
      (fields (field (name "PARTNO") "RC0402FR-071K5L"))
      (libsource (lib "eagle-import") (part "RESISTOR0402-RES"))
    )
    (comp (ref "R404")
      (value "1K5")
      (footprint "eagle-import:0402-RES")
      (fields (field (name "PARTNO") "RC0402FR-071K5L"))
      (libsource (lib "eagle-import") (part "RESISTOR0402-RES"))
    )
    (comp (ref "R405")
      (value "10K/0.1%")
      (footprint "eagle-import:0402-RES")
      (fields (field (name "PARTNO") "ERA-2AEB103X"))
      (libsource (lib "eagle-import") (part "RESISTOR0402-RES"))
    )
    (comp (ref "R406")
      (value "10K/0.1%")
      (footprint "eagle-import:0402-RES")
      (fields (field (name "PARTNO") "ERA-2AEB103X"))
      (libsource (lib "eagle-import") (part "RESISTOR0402-RES"))
    )
    (comp (ref "R407")
      (value "120R")
      (footprint "eagle-import:0402-RES")
      (fields (field (name "PARTNO") "RC0402FR-07120RL"))
      (libsource (lib "eagle-import") (part "RESISTOR0402-RES"))
    )
    (comp (ref "R408")
      (value "120R")
      (footprint "eagle-import:0402-RES")
      (fields (field (name "PARTNO") "RC0402FR-07120RL"))
      (libsource (lib "eagle-import") (part "RESISTOR0402-RES"))
    )
    (comp (ref "SJ401")
      (value "SOLDERJUMPERNC2")
      (footprint "eagle-import:SJ_2S-NOTRACE")
      (libsource (lib "eagle-import") (part "SOLDERJUMPERNC2"))
    )
    (comp (ref "SJ402")
      (value "SOLDERJUMPERNC2")
      (footprint "eagle-import:SJ_2S-NOTRACE")
      (libsource (lib "eagle-import") (part "SOLDERJUMPERNC2"))
    )
    (comp (ref "U$401")
      (value "PESD0402-140")
      (footprint "eagle-import:0402-TVS")
      (libsource (lib "eagle-import") (part "DIODE-TVS"))
    )
    (comp (ref "U$402")
      (value "PESD0402-140")
      (footprint "eagle-import:0402-TVS")
      (libsource (lib "eagle-import") (part "DIODE-TVS"))
    )
    (comp (ref "U401")
      (value "MAX3051")
      (footprint "eagle-import:SOT23-8")
      (fields (field (name "PARTNO") "MAX3051EKA"))
      (libsource (lib "eagle-import") (part "MAX3051MAX3051EKA"))
    )
    (comp (ref "U402")
      (value "MAX3051")
      (footprint "eagle-import:SOT23-8")
      (fields (field (name "PARTNO") "MAX3051EKA"))
      (libsource (lib "eagle-import") (part "MAX3051MAX3051EKA"))
    )
    (comp (ref "C101")
      (value "16p")
      (footprint "eagle-import:0402-CAP")
      (fields (field (name "PARTNO") "C1005C0G1H160"))
      (libsource (lib "eagle-import") (part "CAP0402"))
    )
    (comp (ref "C102")
      (value "16p")
      (footprint "eagle-import:0402-CAP")
      (fields (field (name "PARTNO") "C1005C0G1H160"))
      (libsource (lib "eagle-import") (part "CAP0402"))
    )
    (comp (ref "R101")
      (value "10K")
      (footprint "eagle-import:0402-RES")
      (fields (field (name "PARTNO") "RC0402FR-0710KL"))
      (libsource (lib "eagle-import") (part "RESISTOR0402-RES"))
    )
    (comp (ref "X101")
      (value "3.2x2.5 mm / 24 MHz / 30 ppm / 10pF")
      (footprint "eagle-import:OSCILLATOR-3.2X2.5")
      (fields (field (name "PARTNO") "ABM8G-24.000MHZ-4Y-T3"))
      (libsource (lib "eagle-import") (part "OSCILLATOR-3.2X2.5"))
    )
    (comp (ref "C201")
      (value "0u1")
      (footprint "eagle-import:0402-CAP")
      (fields (field (name "PARTNO") "CC0402ZRY5V7BB104"))
      (libsource (lib "eagle-import") (part "CAP0402"))
    )
    (comp (ref "JP201")
      (value "JUMPER-3SMD")
      (footprint "eagle-import:SJ_3")
      (libsource (lib "eagle-import") (part "JUMPER-3SMD"))
    )
    (comp (ref "JP202")
      (value "HEADER-3X1RA")
      (footprint "eagle-import:3X1RA")
      (libsource (lib "eagle-import") (part "HEADER-3X1RA"))
    )
    (comp (ref "JP203")
      (value "M03X22X3_SILK_SM")
      (footprint "eagle-import:2X3")
      (libsource (lib "eagle-import") (part "M03X22X3_SILK_SM"))
    )
    (comp (ref "JP204")
      (value "M03X22X3_SILK_SM")
      (footprint "eagle-import:2X3")
      (libsource (lib "eagle-import") (part "M03X22X3_SILK_SM"))
    )
    (comp (ref "JP205")
      (value "M03X22X3_SILK_SM")
      (footprint "eagle-import:2X3")
      (libsource (lib "eagle-import") (part "M03X22X3_SILK_SM"))
    )
    (comp (ref "L201")
      (value "NUF8402MN")
      (footprint "eagle-import:DFN16-THIN")
      (fields (field (name "PARTNO") "NUF8402MN"))
      (libsource (lib "eagle-import") (part "NUF8402MN"))
    )
    (comp (ref "L202")
      (value "NUF8402MN")
      (footprint "eagle-import:DFN16-THIN")
      (fields (field (name "PARTNO") "NUF8402MN"))
      (libsource (lib "eagle-import") (part "NUF8402MN"))
    )
    (comp (ref "L203")
      (value "KNH16C104DA5TS")
      (footprint "eagle-import:KYOCERA-KNH16-DA")
      (libsource (lib "eagle-import") (part "KNH16C104DA5TS"))
    )
    (comp (ref "R201")
      (value "120R")
      (footprint "eagle-import:0402-RES")
      (fields (field (name "PARTNO") "RC0402FR-07120RL"))
      (libsource (lib "eagle-import") (part "RESISTOR0402-RES"))
    )
    (comp (ref "R202")
      (value "120R")
      (footprint "eagle-import:0402-RES")
      (fields (field (name "PARTNO") "RC0402FR-07120RL"))
      (libsource (lib "eagle-import") (part "RESISTOR0402-RES"))
    )
    (comp (ref "R203")
      (value "10K")
      (footprint "eagle-import:0402-RES")
      (fields (field (name "PARTNO") "RC0402FR-0710KL"))
      (libsource (lib "eagle-import") (part "RESISTOR0402-RES"))
    )
    (comp (ref "R204")
      (value "10K")
      (footprint "eagle-import:0402-RES")
      (fields (field (name "PARTNO") "RC0402FR-0710KL"))
      (libsource (lib "eagle-import") (part "RESISTOR0402-RES"))
    )
    (comp (ref "U$201")
      (value "PESD0402-140")
      (footprint "eagle-import:0402-TVS")
      (libsource (lib "eagle-import") (part "DIODE-TVS"))
    )
    (comp (ref "U$202")
      (value "PESD0402-140")
      (footprint "eagle-import:0402-TVS")
      (libsource (lib "eagle-import") (part "DIODE-TVS"))
    )
    (comp (ref "U$203")
      (value "74LVC2G240")
      (footprint "eagle-import:VSSOP8")
      (libsource (lib "eagle-import") (part "74LVC2G240"))
    )
    (comp (ref "U$204")
      (value "PESD0402-140")
      (footprint "eagle-import:0402-TVS")
      (libsource (lib "eagle-import") (part "DIODE-TVS"))
    )
    (comp (ref "JP801")
      (value "M03PTH")
      (footprint "eagle-import:1X03")
      (libsource (lib "eagle-import") (part "M03PTH"))
    )
    (comp (ref "LED801")
      (value "AMBER")
      (footprint "eagle-import:0603-LED")
      (fields (field (name "PARTNO") "APTD1608SECK"))
      (libsource (lib "eagle-import") (part "LED0603"))
    )
    (comp (ref "LED802")
      (value "GREEN")
      (footprint "eagle-import:0603-LED")
      (fields (field (name "PARTNO") "APTD1608CGCK"))
      (libsource (lib "eagle-import") (part "LED0603"))
    )
    (comp (ref "R801")
      (value "47R")
      (footprint "eagle-import:0402-RES")
      (fields (field (name "PARTNO") "RC0402JR-0747RL"))
      (libsource (lib "eagle-import") (part "RESISTOR0402-RES"))
    )
    (comp (ref "R802")
      (value "1K5")
      (footprint "eagle-import:0402-RES")
      (fields (field (name "PARTNO") "RC0402FR-071K5L"))
      (libsource (lib "eagle-import") (part "RESISTOR0402-RES"))
    )
    (comp (ref "R803")
      (value "220R")
      (footprint "eagle-import:0402-RES")
      (fields (field (name "PARTNO") "RC0402FR-07220RL"))
      (libsource (lib "eagle-import") (part "RESISTOR0402-RES"))
    )
    (comp (ref "R804")
      (value "220R")
      (footprint "eagle-import:0402-RES")
      (fields (field (name "PARTNO") "RC0402FR-07220RL"))
      (libsource (lib "eagle-import") (part "RESISTOR0402-RES"))
    )
    (comp (ref "R805")
      (value "220R")
      (footprint "eagle-import:0402-RES")
      (fields (field (name "PARTNO") "RC0402FR-07220RL"))
      (libsource (lib "eagle-import") (part "RESISTOR0402-RES"))
    )
    (comp (ref "U$801")
      (value "PESD0402-140")
      (footprint "eagle-import:0402-TVS")
      (libsource (lib "eagle-import") (part "DIODE-TVS"))
    )
    (comp (ref "J1001")
      (value "SERVO_HEADER-3X8")
      (footprint "eagle-import:3X8RA_SERVO")
      (fields (field (name "BOM") "EXCLUDE"))
      (libsource (lib "eagle-import") (part "SERVO_HEADER-3X8"))
    )
    (comp (ref "JP1001")
      (value "M01SMD-4.5X1.5")
      (footprint "eagle-import:PAD-1.5X4.5")
      (libsource (lib "eagle-import") (part "M01SMD-4.5X1.5"))
    )
    (comp (ref "JP1002")
      (value "M01SMD-4.5X1.5")
      (footprint "eagle-import:PAD-1.5X4.5")
      (libsource (lib "eagle-import") (part "M01SMD-4.5X1.5"))
    )
    (comp (ref "L1001")
      (value "NUF8402MN")
      (footprint "eagle-import:DFN16-THIN")
      (fields (field (name "PARTNO") "NUF8402MN"))
      (libsource (lib "eagle-import") (part "NUF8402MN"))
    )
    (comp (ref "R1001")
      (value "220R")
      (footprint "eagle-import:0402-RES")
      (fields (field (name "PARTNO") "RC0402FR-07220RL"))
      (libsource (lib "eagle-import") (part "RESISTOR0402-RES"))
    )
    (comp (ref "R1002")
      (value "220R")
      (footprint "eagle-import:0402-RES")
      (fields (field (name "PARTNO") "RC0402FR-07220RL"))
      (libsource (lib "eagle-import") (part "RESISTOR0402-RES"))
    )
    (comp (ref "C601")
      (value "22uF")
      (footprint "eagle-import:1210")
      (fields (field (name "PARTNO") "C3225X7R1C226M250AC"))
      (libsource (lib "eagle-import") (part "22UF-16V-20%-(1210)"))
    )
    (comp (ref "C602")
      (value "0u1")
      (footprint "eagle-import:0402-CAP")
      (fields (field (name "PARTNO") "CC0402ZRY5V7BB104"))
      (libsource (lib "eagle-import") (part "CAP0402"))
    )
    (comp (ref "C603")
      (value "0u1")
      (footprint "eagle-import:0402-CAP")
      (fields (field (name "PARTNO") "CC0402ZRY5V7BB104"))
      (libsource (lib "eagle-import") (part "CAP0402"))
    )
    (comp (ref "C604")
      (value "22uF")
      (footprint "eagle-import:1210")
      (fields (field (name "PARTNO") "C3225X7R1C226M250AC"))
      (libsource (lib "eagle-import") (part "22UF-16V-20%-(1210)"))
    )
    (comp (ref "C605")
      (value "22uF")
      (footprint "eagle-import:1210")
      (fields (field (name "PARTNO") "C3225X7R1C226M250AC"))
      (libsource (lib "eagle-import") (part "22UF-16V-20%-(1210)"))
    )
    (comp (ref "C606")
      (value "22uF")
      (footprint "eagle-import:1210")
      (fields (field (name "PARTNO") "C3225X7R1C226M250AC"))
      (libsource (lib "eagle-import") (part "22UF-16V-20%-(1210)"))
    )
    (comp (ref "L$601")
      (value "XFL4020-222MEB")
      (footprint "eagle-import:XFL4020")
      (libsource (lib "eagle-import") (part "XFL4020-222MEB"))
    )
    (comp (ref "U$601")
      (value "TPS6303X")
      (footprint "eagle-import:PWSON10")
      (fields (field (name "PARTNO") "TPS63061DSCT"))
      (libsource (lib "eagle-import") (part "TPS6303X"))
    )
    (comp (ref "C301")
      (value "2u2")
      (footprint "eagle-import:0603-CAP")
      (fields (field (name "PARTNO") "C1608Y5V1C225Z"))
      (libsource (lib "eagle-import") (part "CAP0603"))
    )
    (comp (ref "C302")
      (value "0u1")
      (footprint "eagle-import:0402-CAP")
      (fields (field (name "PARTNO") "CC0402ZRY5V7BB104"))
      (libsource (lib "eagle-import") (part "CAP0402"))
    )
    (comp (ref "JP301")
      (value "M04PTH")
      (footprint "eagle-import:1X04")
      (libsource (lib "eagle-import") (part "M04PTH"))
    )
    (comp (ref "JX301")
      (value "ARM_MINI_JTAG-SMT")
      (footprint "eagle-import:FTSH-105-01-XXX-DV-K")
      (fields (field (name "BOM") "EXCLUDE") (field (name "PARTNO") "M50-3900542"))
      (libsource (lib "eagle-import") (part "ARM_MINI_JTAG-SMT"))
    )
    (comp (ref "U$301")
      (value "NUF2042XV6")
      (footprint "eagle-import:SOT563-6")
      (libsource (lib "eagle-import") (part "NUF2042XV6"))
    )
    (comp (ref "U$302")
      (value "W25Q64FV")
      (footprint "eagle-import:WSON-8-5X6")
      (fields (field (name "PARTNO") "W25Q64FVZP"))
      (libsource (lib "eagle-import") (part "W25Q64FV"))
    )
    (comp (ref "JP1101")
      (value "FIDUCIAL1.5X3")
      (footprint "eagle-import:FIDUCIAL-1.5X3")
      (libsource (lib "eagle-import") (part "FIDUCIAL1.5X3"))
    )
    (comp (ref "JP1102")
      (value "FIDUCIAL1.5X3")
      (footprint "eagle-import:FIDUCIAL-1.5X3")
      (libsource (lib "eagle-import") (part "FIDUCIAL1.5X3"))
    )
    (comp (ref "JP1103")
      (value "FIDUCIAL1.5X3")
      (footprint "eagle-import:FIDUCIAL-1.5X3")
      (libsource (lib "eagle-import") (part "FIDUCIAL1.5X3"))
    )
    (comp (ref "JP1104")
      (value "FIDUCIAL1.5X3")
      (footprint "eagle-import:FIDUCIAL-1.5X3")
      (libsource (lib "eagle-import") (part "FIDUCIAL1.5X3"))
    )
    (comp (ref "JP1105")
      (value "M01PTH")
      (footprint "eagle-import:1X01")
      (libsource (lib "eagle-import") (part "M01PTH"))
    )
    (comp (ref "M3_MOUNT1101")
      (value "MOUNT-HOLE3.1MM")
      (footprint "eagle-import:MOUNT-HOLE3.1")
      (libsource (lib "eagle-import") (part "MOUNT-HOLE3.1MM"))
    )
    (comp (ref "M3_MOUNT1102")
      (value "MOUNT-HOLE3.1MM")
      (footprint "eagle-import:MOUNT-HOLE3.1")
      (libsource (lib "eagle-import") (part "MOUNT-HOLE3.1MM"))
    )
    (comp (ref "M3_MOUNT1103")
      (value "MOUNT-HOLE3.1MM")
      (footprint "eagle-import:MOUNT-HOLE3.1")
      (libsource (lib "eagle-import") (part "MOUNT-HOLE3.1MM"))
    )
    (comp (ref "M3_MOUNT1104")
      (value "MOUNT-HOLE3.1MM")
      (footprint "eagle-import:MOUNT-HOLE3.1")
      (libsource (lib "eagle-import") (part "MOUNT-HOLE3.1MM"))
    )
    (comp (ref "OSHW_LOGO")
      (value "OSHW-LOGOS")
      (footprint "eagle-import:OSHW-LOGO-S")
      (libsource (lib "eagle-import") (part "OSHW-LOGOS"))
    )
    (comp (ref "C501")
      (value "10u/10V")
      (footprint "eagle-import:0805-CAP")
      (fields (field (name "PARTNO") "CC0805ZKY5V6BB106"))
      (libsource (lib "eagle-import") (part "CAP0805"))
    )
    (comp (ref "C502")
      (value "10n")
      (footprint "eagle-import:0402-CAP")
      (fields (field (name "PARTNO") "CC0402KRX7R7BB103"))
      (libsource (lib "eagle-import") (part "CAP0402"))
    )
    (comp (ref "C503")
      (value "0u1")
      (footprint "eagle-import:0402-CAP")
      (fields (field (name "PARTNO") "CC0402ZRY5V7BB104"))
      (libsource (lib "eagle-import") (part "CAP0402"))
    )
    (comp (ref "U$501")
      (value "MAX21100")
      (footprint "eagle-import:16LGA-3X3")
      (fields (field (name "PARTNO") "MAX21100+"))
      (libsource (lib "eagle-import") (part "MAX21100"))
    )
  )
  (nets
    (net (code "1") (name "ACCEL_DRDY") (class "Default")
      (node (ref "U$501") (pin "11") (pinfunction "INT1_11") (pintype "bidirectional"))
      (node (ref "U101") (pin "90") (pinfunction "PB4_90") (pintype "bidirectional"))
    )
    (net (code "2") (name "ALARM") (class "Default")
      (node (ref "U101") (pin "77") (pinfunction "PA15_77") (pintype "bidirectional"))
    )
    (net (code "3") (name "CAN1_H") (class "Default")
      (node (ref "JP405") (pin "2") (pinfunction "2_2") (pintype "passive"))
      (node (ref "R407") (pin "P$1") (pinfunction "1_P$1") (pintype "passive"))
      (node (ref "U402") (pin "7") (pinfunction "CANH_7") (pintype "bidirectional"))
    )
    (net (code "4") (name "CAN1_L") (class "Default")
      (node (ref "JP405") (pin "3") (pinfunction "3_3") (pintype "passive"))
      (node (ref "SJ402") (pin "2") (pinfunction "2_2") (pintype "passive"))
      (node (ref "U402") (pin "6") (pinfunction "CANL_6") (pintype "bidirectional"))
    )
    (net (code "5") (name "CAN1_RX") (class "Default")
      (node (ref "U101") (pin "81") (pinfunction "PD0_81") (pintype "bidirectional"))
      (node (ref "U402") (pin "4") (pinfunction "DOUT_4") (pintype "output"))
    )
    (net (code "6") (name "CAN1_TX") (class "Default")
      (node (ref "U101") (pin "82") (pinfunction "PD1_82") (pintype "bidirectional"))
      (node (ref "U402") (pin "1") (pinfunction "DIN_1") (pintype "input"))
    )
    (net (code "7") (name "CAN2_RX") (class "Default")
      (node (ref "U101") (pin "51") (pinfunction "PB12_51") (pintype "bidirectional"))
      (node (ref "U401") (pin "4") (pinfunction "DOUT_4") (pintype "output"))
    )
    (net (code "8") (name "CAN2_TX") (class "Default")
      (node (ref "U101") (pin "92") (pinfunction "PB6_92") (pintype "bidirectional"))
      (node (ref "U401") (pin "1") (pinfunction "DIN_1") (pintype "input"))
    )
    (net (code "9") (name "FMU-BOOT0") (class "Default")
      (node (ref "JP1105") (pin "1") (pinfunction "1_1") (pintype "passive"))
      (node (ref "R709") (pin "P$2") (pinfunction "2_P$2") (pintype "passive"))
      (node (ref "U101") (pin "94") (pinfunction "BOOT0_94") (pintype "input"))
    )
    (net (code "10") (name "FMU-CH1") (class "Default")
      (node (ref "L1001") (pin "P$4") (pinfunction "P$1_P$4") (pintype "bidirectional"))
      (node (ref "U101") (pin "45") (pinfunction "PE14_45") (pintype "bidirectional"))
    )
    (net (code "11") (name "FMU-CH2") (class "Default")
      (node (ref "L1001") (pin "P$5") (pinfunction "P$1_P$5") (pintype "bidirectional"))
      (node (ref "U101") (pin "44") (pinfunction "PE13_44") (pintype "bidirectional"))
    )
    (net (code "12") (name "FMU-CH3") (class "Default")
      (node (ref "L1001") (pin "P$6") (pinfunction "P$1_P$6") (pintype "bidirectional"))
      (node (ref "U101") (pin "42") (pinfunction "PE11_42") (pintype "bidirectional"))
    )
    (net (code "13") (name "FMU-CH4") (class "Default")
      (node (ref "L1001") (pin "P$7") (pinfunction "P$1_P$7") (pintype "bidirectional"))
      (node (ref "U101") (pin "40") (pinfunction "PE9_40") (pintype "bidirectional"))
    )
    (net (code "14") (name "FMU-CH5") (class "Default")
      (node (ref "L1001") (pin "P$2") (pinfunction "P$1_P$2") (pintype "bidirectional"))
      (node (ref "U101") (pin "60") (pinfunction "PD13_60") (pintype "bidirectional"))
    )
    (net (code "15") (name "FMU-CH6") (class "Default")
      (node (ref "L1001") (pin "P$3") (pinfunction "P$1_P$3") (pintype "bidirectional"))
      (node (ref "U101") (pin "62") (pinfunction "PD15_62") (pintype "bidirectional"))
    )
    (net (code "16") (name "FMU-CH7") (class "Default")
      (node (ref "L1001") (pin "P$8") (pinfunction "P$1_P$8") (pintype "bidirectional"))
      (node (ref "U101") (pin "24") (pinfunction "PA1_24") (pintype "bidirectional"))
    )
    (net (code "17") (name "FMU-CH8") (class "Default")
      (node (ref "L1001") (pin "P$1") (pinfunction "P$1_P$1") (pintype "bidirectional"))
      (node (ref "U$203") (pin "3") (pinfunction "2Y_3") (pintype "bidirectional"))
      (node (ref "U101") (pin "61") (pinfunction "PD14_61") (pintype "bidirectional"))
    )
    (net (code "18") (name "FMU-CH9") (class "Default")
      (node (ref "R1001") (pin "P$2") (pinfunction "2_P$2") (pintype "passive"))
      (node (ref "U101") (pin "25") (pinfunction "PA2_25") (pintype "bidirectional"))
    )
    (net (code "19") (name "FMU-CH10") (class "Default")
      (node (ref "R1002") (pin "P$2") (pinfunction "2_P$2") (pintype "passive"))
      (node (ref "U101") (pin "26") (pinfunction "PA3_26") (pintype "bidirectional"))
    )
    (net (code "20") (name "FMU-I2C1_SCL") (class "Default")
      (node (ref "L403") (pin "P$2") (pinfunction "P$1_P$2") (pintype "bidirectional"))
      (node (ref "R402") (pin "P$1") (pinfunction "1_P$1") (pintype "passive"))
      (node (ref "U101") (pin "95") (pinfunction "PB8_95") (pintype "bidirectional"))
    )
    (net (code "21") (name "FMU-I2C1_SDA") (class "Default")
      (node (ref "L403") (pin "P$7") (pinfunction "P$1_P$7") (pintype "bidirectional"))
      (node (ref "R404") (pin "P$1") (pinfunction "1_P$1") (pintype "passive"))
      (node (ref "U101") (pin "96") (pinfunction "PB9_96") (pintype "bidirectional"))
    )
    (net (code "22") (name "FMU-I2C2_SCL") (class "Default")
      (node (ref "L403") (pin "P$4") (pinfunction "P$1_P$4") (pintype "bidirectional"))
      (node (ref "R401") (pin "P$1") (pinfunction "1_P$1") (pintype "passive"))
      (node (ref "U101") (pin "47") (pinfunction "PB10_47") (pintype "bidirectional"))
    )
    (net (code "23") (name "FMU-I2C2_SDA") (class "Default")
      (node (ref "L403") (pin "P$8") (pinfunction "P$1_P$8") (pintype "bidirectional"))
      (node (ref "R403") (pin "P$1") (pinfunction "1_P$1") (pintype "passive"))
      (node (ref "U101") (pin "48") (pinfunction "PB11_48") (pintype "bidirectional"))
    )
    (net (code "24") (name "FMU-LED_SAFETY") (class "Default")
      (node (ref "R801") (pin "P$2") (pinfunction "2_P$2") (pintype "passive"))
      (node (ref "U101") (pin "9") (pinfunction "PC15_9") (pintype "bidirectional"))
    )
    (net (code "25") (name "FMU-SWCLK") (class "Default")
      (node (ref "JX301") (pin "4") (pinfunction "S_4") (pintype "passive"))
      (node (ref "U101") (pin "76") (pinfunction "PA14_76") (pintype "bidirectional"))
    )
    (net (code "26") (name "FMU-SWDIO") (class "Default")
      (node (ref "JX301") (pin "2") (pinfunction "S_2") (pintype "passive"))
      (node (ref "U101") (pin "72") (pinfunction "PA13_72") (pintype "bidirectional"))
    )
    (net (code "27") (name "FMU-SWO") (class "Default")
      (node (ref "JX301") (pin "6") (pinfunction "S_6") (pintype "passive"))
      (node (ref "U101") (pin "89") (pinfunction "PB3_89") (pintype "bidirectional"))
    )
    (net (code "28") (name "FMU-UART7_RX") (class "Default")
      (node (ref "L202") (pin "P$8") (pinfunction "P$1_P$8") (pintype "bidirectional"))
      (node (ref "U101") (pin "38") (pinfunction "PE7_38") (pintype "bidirectional"))
    )
    (net (code "29") (name "FMU-UART7_TX") (class "Default")
      (node (ref "L202") (pin "P$6") (pinfunction "P$1_P$6") (pintype "bidirectional"))
      (node (ref "U101") (pin "39") (pinfunction "PE8_39") (pintype "bidirectional"))
    )
    (net (code "30") (name "FMU-UART8_RX") (class "Default")
      (node (ref "U$203") (pin "6") (pinfunction "1Y_6") (pintype "bidirectional"))
      (node (ref "U101") (pin "97") (pinfunction "PE0_97") (pintype "bidirectional"))
    )
    (net (code "31") (name "FMU-UART8_TX") (class "Default")
      (node (ref "U$203") (pin "5") (pinfunction "2A_5") (pintype "bidirectional"))
      (node (ref "U101") (pin "98") (pinfunction "PE1_98") (pintype "bidirectional"))
    )
    (net (code "32") (name "FMU-USART2_CTS") (class "Default")
      (node (ref "L201") (pin "P$1") (pinfunction "P$1_P$1") (pintype "bidirectional"))
      (node (ref "U101") (pin "84") (pinfunction "PD3_84") (pintype "bidirectional"))
    )
    (net (code "33") (name "FMU-USART2_RTS") (class "Default")
      (node (ref "L201") (pin "P$2") (pinfunction "P$1_P$2") (pintype "bidirectional"))
      (node (ref "U101") (pin "85") (pinfunction "PD4_85") (pintype "bidirectional"))
    )
    (net (code "34") (name "FMU-USART2_RX") (class "Default")
      (node (ref "L201") (pin "P$4") (pinfunction "P$1_P$4") (pintype "bidirectional"))
      (node (ref "U101") (pin "87") (pinfunction "PD6_87") (pintype "bidirectional"))
    )
    (net (code "35") (name "FMU-USART2_TX") (class "Default")
      (node (ref "L201") (pin "P$3") (pinfunction "P$1_P$3") (pintype "bidirectional"))
      (node (ref "U101") (pin "86") (pinfunction "PD5_86") (pintype "bidirectional"))
    )
    (net (code "36") (name "FMU-USART3_CTS") (class "Default")
      (node (ref "L201") (pin "P$7") (pinfunction "P$1_P$7") (pintype "bidirectional"))
      (node (ref "U101") (pin "58") (pinfunction "PD11_58") (pintype "bidirectional"))
    )
    (net (code "37") (name "FMU-USART3_RTS") (class "Default")
      (node (ref "L201") (pin "P$8") (pinfunction "P$1_P$8") (pintype "bidirectional"))
      (node (ref "U101") (pin "59") (pinfunction "PD12_59") (pintype "bidirectional"))
    )
    (net (code "38") (name "FMU-USART3_RX") (class "Default")
      (node (ref "L201") (pin "P$6") (pinfunction "P$1_P$6") (pintype "bidirectional"))
      (node (ref "U101") (pin "56") (pinfunction "PD9_56") (pintype "bidirectional"))
    )
    (net (code "39") (name "FMU-USART3_TX") (class "Default")
      (node (ref "L201") (pin "P$5") (pinfunction "P$1_P$5") (pintype "bidirectional"))
      (node (ref "U101") (pin "55") (pinfunction "PD8_55") (pintype "bidirectional"))
    )
    (net (code "40") (name "FMU-VDD_3V3") (class "Default")
      (node (ref "C201") (pin "P$1") (pinfunction "1_P$1") (pintype "passive"))
      (node (ref "C301") (pin "P$1") (pinfunction "1_P$1") (pintype "passive"))
      (node (ref "C302") (pin "P$1") (pinfunction "1_P$1") (pintype "passive"))
      (node (ref "C401") (pin "P$1") (pinfunction "1_P$1") (pintype "passive"))
      (node (ref "C402") (pin "P$1") (pinfunction "1_P$1") (pintype "passive"))
      (node (ref "C705") (pin "P$1") (pinfunction "1_P$1") (pintype "passive"))
      (node (ref "C706") (pin "P$1") (pinfunction "1_P$1") (pintype "passive"))
      (node (ref "C709") (pin "P$1") (pinfunction "1_P$1") (pintype "passive"))
      (node (ref "C710") (pin "P$1") (pinfunction "1_P$1") (pintype "passive"))
      (node (ref "C711") (pin "P$1") (pinfunction "1_P$1") (pintype "passive"))
      (node (ref "C712") (pin "P$1") (pinfunction "1_P$1") (pintype "passive"))
      (node (ref "C714") (pin "P$1") (pinfunction "1_P$1") (pintype "passive"))
      (node (ref "C716") (pin "P$1") (pinfunction "1_P$1") (pintype "passive"))
      (node (ref "D701") (pin "A") (pinfunction "A_A") (pintype "passive"))
      (node (ref "JP801") (pin "1") (pinfunction "1_1") (pintype "passive"))
      (node (ref "JX301") (pin "1") (pinfunction "S_1") (pintype "passive"))
      (node (ref "R401") (pin "P$2") (pinfunction "2_P$2") (pintype "passive"))
      (node (ref "R402") (pin "P$2") (pinfunction "2_P$2") (pintype "passive"))
      (node (ref "R403") (pin "P$2") (pinfunction "2_P$2") (pintype "passive"))
      (node (ref "R404") (pin "P$2") (pinfunction "2_P$2") (pintype "passive"))
      (node (ref "R702") (pin "P$1") (pinfunction "1_P$1") (pintype "passive"))
      (node (ref "R704") (pin "P$1") (pinfunction "1_P$1") (pintype "passive"))
      (node (ref "R705") (pin "P$1") (pinfunction "1_P$1") (pintype "passive"))
      (node (ref "U$203") (pin "8") (pinfunction "VCC_8") (pintype "power_in"))
      (node (ref "U$302") (pin "8") (pinfunction "VCC_8") (pintype "bidirectional"))
      (node (ref "U$701") (pin "7") (pinfunction "VOUT2_7") (pintype "bidirectional"))
      (node (ref "U$801") (pin "C") (pinfunction "C_C") (pintype "passive"))
      (node (ref "U101") (pin "100") (pinfunction "VDD_100") (pintype "power_in"))
      (node (ref "U101") (pin "11") (pinfunction "VDD_11") (pintype "power_in"))
      (node (ref "U101") (pin "19") (pinfunction "VDD_19") (pintype "power_in"))
      (node (ref "U101") (pin "21") (pinfunction "VREF+_21") (pintype "input"))
      (node (ref "U101") (pin "22") (pinfunction "VDDA_22") (pintype "power_in"))
      (node (ref "U101") (pin "28") (pinfunction "VDD_28") (pintype "power_in"))
      (node (ref "U101") (pin "50") (pinfunction "VDD_50") (pintype "power_in"))
      (node (ref "U101") (pin "75") (pinfunction "VDD_75") (pintype "power_in"))
      (node (ref "U401") (pin "3") (pinfunction "VCC_3") (pintype "input"))
      (node (ref "U402") (pin "3") (pinfunction "VCC_3") (pintype "input"))
    )
    (net (code "41") (name "FMU-~{RESET}") (class "Default")
      (node (ref "C713") (pin "P$2") (pinfunction "2_P$2") (pintype "passive"))
      (node (ref "JX301") (pin "10") (pinfunction "S_10") (pintype "passive"))
      (node (ref "S701") (pin "A1") (pinfunction "1_A1") (pintype "passive"))
      (node (ref "U$701") (pin "3") (pinfunction "POR2_3") (pintype "bidirectional"))
      (node (ref "U101") (pin "14") (pinfunction "NRST_14") (pintype "input"))
    )
    (net (code "42") (name "FMU_AUX_ADC1") (class "Default")
      (node (ref "R405") (pin "P$1") (pinfunction "1_P$1") (pintype "passive"))
      (node (ref "U101") (pin "18") (pinfunction "PC3_18") (pintype "bidirectional"))
    )
    (net (code "43") (name "FMU_AUX_ADC2") (class "Default")
      (node (ref "R406") (pin "P$1") (pinfunction "1_P$1") (pintype "passive"))
      (node (ref "U101") (pin "33") (pinfunction "PC4_33") (pintype "bidirectional"))
    )
    (net (code "44") (name "FRAM_MISO") (class "Default")
      (node (ref "U101") (pin "53") (pinfunction "PB14_53") (pintype "bidirectional"))
    )
    (net (code "45") (name "FRAM_MOSI") (class "Default")
      (node (ref "U101") (pin "54") (pinfunction "PB15_54") (pintype "bidirectional"))
    )
    (net (code "46") (name "FRAM_SCK") (class "Default")
      (node (ref "U101") (pin "52") (pinfunction "PB13_52") (pintype "bidirectional"))
    )
    (net (code "47") (name "GND") (class "Default")
      (node (ref "C101") (pin "P$2") (pinfunction "2_P$2") (pintype "passive"))
      (node (ref "C102") (pin "P$1") (pinfunction "1_P$1") (pintype "passive"))
      (node (ref "C201") (pin "P$2") (pinfunction "2_P$2") (pintype "passive"))
      (node (ref "C301") (pin "P$2") (pinfunction "2_P$2") (pintype "passive"))
      (node (ref "C302") (pin "P$2") (pinfunction "2_P$2") (pintype "passive"))
      (node (ref "C401") (pin "P$2") (pinfunction "2_P$2") (pintype "passive"))
      (node (ref "C402") (pin "P$2") (pinfunction "2_P$2") (pintype "passive"))
      (node (ref "C403") (pin "P$2") (pinfunction "2_P$2") (pintype "passive"))
      (node (ref "C404") (pin "P$2") (pinfunction "2_P$2") (pintype "passive"))
      (node (ref "C501") (pin "P$2") (pinfunction "2_P$2") (pintype "passive"))
      (node (ref "C502") (pin "P$2") (pinfunction "2_P$2") (pintype "passive"))
      (node (ref "C503") (pin "P$2") (pinfunction "2_P$2") (pintype "passive"))
      (node (ref "C601") (pin "2") (pinfunction "2_2") (pintype "passive"))
      (node (ref "C602") (pin "P$2") (pinfunction "2_P$2") (pintype "passive"))
      (node (ref "C603") (pin "P$2") (pinfunction "2_P$2") (pintype "passive"))
      (node (ref "C604") (pin "2") (pinfunction "2_2") (pintype "passive"))
      (node (ref "C605") (pin "2") (pinfunction "2_2") (pintype "passive"))
      (node (ref "C606") (pin "2") (pinfunction "2_2") (pintype "passive"))
      (node (ref "C701") (pin "P$2") (pinfunction "2_P$2") (pintype "passive"))
      (node (ref "C702") (pin "P$2") (pinfunction "2_P$2") (pintype "passive"))
      (node (ref "C703") (pin "P$1") (pinfunction "1_P$1") (pintype "passive"))
      (node (ref "C704") (pin "P$2") (pinfunction "2_P$2") (pintype "passive"))
      (node (ref "C705") (pin "P$2") (pinfunction "2_P$2") (pintype "passive"))
      (node (ref "C706") (pin "P$2") (pinfunction "2_P$2") (pintype "passive"))
      (node (ref "C707") (pin "P$2") (pinfunction "2_P$2") (pintype "passive"))
      (node (ref "C708") (pin "P$2") (pinfunction "2_P$2") (pintype "passive"))
      (node (ref "C709") (pin "P$2") (pinfunction "2_P$2") (pintype "passive"))
      (node (ref "C710") (pin "P$2") (pinfunction "2_P$2") (pintype "passive"))
      (node (ref "C711") (pin "P$2") (pinfunction "2_P$2") (pintype "passive"))
      (node (ref "C712") (pin "P$2") (pinfunction "2_P$2") (pintype "passive"))
      (node (ref "C713") (pin "P$1") (pinfunction "1_P$1") (pintype "passive"))
      (node (ref "C714") (pin "P$2") (pinfunction "2_P$2") (pintype "passive"))
      (node (ref "C715") (pin "P$2") (pinfunction "2_P$2") (pintype "passive"))
      (node (ref "C716") (pin "P$2") (pinfunction "2_P$2") (pintype "passive"))
      (node (ref "C717") (pin "P$2") (pinfunction "2_P$2") (pintype "passive"))
      (node (ref "D901") (pin "A") (pinfunction "A_A") (pintype "passive"))
      (node (ref "J1001") (pin "GND_S1") (pinfunction "S_GND_S1") (pintype "passive"))
      (node (ref "J1001") (pin "GND_S2") (pinfunction "S_GND_S2") (pintype "passive"))
      (node (ref "J1001") (pin "GND_S3") (pinfunction "S_GND_S3") (pintype "passive"))
      (node (ref "J1001") (pin "GND_S4") (pinfunction "S_GND_S4") (pintype "passive"))
      (node (ref "J1001") (pin "GND_S5") (pinfunction "S_GND_S5") (pintype "passive"))
      (node (ref "J1001") (pin "GND_S6") (pinfunction "S_GND_S6") (pintype "passive"))
      (node (ref "J1001") (pin "GND_S7") (pinfunction "S_GND_S7") (pintype "passive"))
      (node (ref "J1001") (pin "GND_S8") (pinfunction "S_GND_S8") (pintype "passive"))
      (node (ref "J401") (pin "7") (pinfunction "7_7") (pintype "passive"))
      (node (ref "JP202") (pin "3") (pinfunction "3_3") (pintype "bidirectional"))
      (node (ref "JP203") (pin "5") (pinfunction "5_5") (pintype "bidirectional"))
      (node (ref "JP204") (pin "5") (pinfunction "5_5") (pintype "bidirectional"))
      (node (ref "JP205") (pin "5") (pinfunction "5_5") (pintype "bidirectional"))
      (node (ref "JP301") (pin "4") (pinfunction "4_4") (pintype "passive"))
      (node (ref "JP401") (pin "4") (pinfunction "4_4") (pintype "passive"))
      (node (ref "JP402") (pin "4") (pinfunction "4_4") (pintype "passive"))
      (node (ref "JP403") (pin "3") (pinfunction "3_3") (pintype "passive"))
      (node (ref "JP404") (pin "4") (pinfunction "4_4") (pintype "passive"))
      (node (ref "JP405") (pin "4") (pinfunction "4_4") (pintype "passive"))
      (node (ref "JP901") (pin "2") (pinfunction "2_2") (pintype "passive"))
      (node (ref "JX301") (pin "3") (pinfunction "S_3") (pintype "passive"))
      (node (ref "JX301") (pin "5") (pinfunction "S_5") (pintype "passive"))
      (node (ref "JX301") (pin "9") (pinfunction "S_9") (pintype "passive"))
      (node (ref "L1001") (pin "P$EP") (pinfunction "GND_P$EP") (pintype "power_in"))
      (node (ref "L201") (pin "P$EP") (pinfunction "GND_P$EP") (pintype "power_in"))
      (node (ref "L202") (pin "P$EP") (pinfunction "GND_P$EP") (pintype "power_in"))
      (node (ref "L203") (pin "P$3") (pinfunction "P$3_P$3") (pintype "bidirectional"))
      (node (ref "L203") (pin "P$4") (pinfunction "P$3_P$4") (pintype "bidirectional"))
      (node (ref "L203") (pin "P$5") (pinfunction "P$3_P$5") (pintype "bidirectional"))
      (node (ref "L401") (pin "P$3") (pinfunction "P$3_P$3") (pintype "bidirectional"))
      (node (ref "L401") (pin "P$4") (pinfunction "P$3_P$4") (pintype "bidirectional"))
      (node (ref "L401") (pin "P$5") (pinfunction "P$3_P$5") (pintype "bidirectional"))
      (node (ref "L402") (pin "P$3") (pinfunction "P$3_P$3") (pintype "bidirectional"))
      (node (ref "L402") (pin "P$4") (pinfunction "P$3_P$4") (pintype "bidirectional"))
      (node (ref "L402") (pin "P$5") (pinfunction "P$3_P$5") (pintype "bidirectional"))
      (node (ref "L403") (pin "P$EP") (pinfunction "GND_P$EP") (pintype "power_in"))
      (node (ref "L404") (pin "P$3") (pinfunction "P$3_P$3") (pintype "bidirectional"))
      (node (ref "L404") (pin "P$4") (pinfunction "P$3_P$4") (pintype "bidirectional"))
      (node (ref "L404") (pin "P$5") (pinfunction "P$3_P$5") (pintype "bidirectional"))
      (node (ref "R101") (pin "P$2") (pinfunction "2_P$2") (pintype "passive"))
      (node (ref "R203") (pin "P$2") (pinfunction "2_P$2") (pintype "passive"))
      (node (ref "R204") (pin "P$1") (pinfunction "1_P$1") (pintype "passive"))
      (node (ref "R701") (pin "P$1") (pinfunction "1_P$1") (pintype "passive"))
      (node (ref "R703") (pin "P$2") (pinfunction "2_P$2") (pintype "passive"))
      (node (ref "R708") (pin "P$2") (pinfunction "2_P$2") (pintype "passive"))
      (node (ref "R709") (pin "P$1") (pinfunction "1_P$1") (pintype "passive"))
      (node (ref "R802") (pin "P$2") (pinfunction "2_P$2") (pintype "passive"))
      (node (ref "R805") (pin "P$1") (pinfunction "1_P$1") (pintype "passive"))
      (node (ref "R903") (pin "P$1") (pinfunction "1_P$1") (pintype "passive"))
      (node (ref "S701") (pin "B3") (pinfunction "2_B3") (pintype "passive"))
      (node (ref "U$201") (pin "A") (pinfunction "A_A") (pintype "passive"))
      (node (ref "U$202") (pin "A") (pinfunction "A_A") (pintype "passive"))
      (node (ref "U$203") (pin "1") (pinfunction "~{1OE}_1") (pintype "input"))
      (node (ref "U$203") (pin "4") (pinfunction "GND_4") (pintype "power_in"))
      (node (ref "U$204") (pin "A") (pinfunction "A_A") (pintype "passive"))
      (node (ref "U$301") (pin "2") (pinfunction "GND_2") (pintype "bidirectional"))
      (node (ref "U$302") (pin "4") (pinfunction "GND_4") (pintype "bidirectional"))
      (node (ref "U$302") (pin "PAD") (pinfunction "GND_PAD") (pintype "bidirectional"))
      (node (ref "U$401") (pin "A") (pinfunction "A_A") (pintype "passive"))
      (node (ref "U$402") (pin "A") (pinfunction "A_A") (pintype "passive"))
      (node (ref "U$501") (pin "10") (pinfunction "RSV1_10") (pintype "input"))
      (node (ref "U$501") (pin "5") (pinfunction "GND_5") (pintype "power_in"))
      (node (ref "U$601") (pin "11") (pinfunction "GND_11") (pintype "power_in"))
      (node (ref "U$601") (pin "15") (pinfunction "PGND_15") (pintype "power_in"))
      (node (ref "U$601") (pin "16") (pinfunction "PGND_16") (pintype "power_in"))
      (node (ref "U$601") (pin "17") (pinfunction "PGND_17") (pintype "power_in"))
      (node (ref "U$601") (pin "18") (pinfunction "PGND_18") (pintype "power_in"))
      (node (ref "U$601") (pin "19") (pinfunction "PGND_19") (pintype "power_in"))
      (node (ref "U$601") (pin "20") (pinfunction "PGND_20") (pintype "power_in"))
      (node (ref "U$601") (pin "21") (pinfunction "PGND_21") (pintype "power_in"))
      (node (ref "U$601") (pin "22") (pinfunction "PGND_22") (pintype "power_in"))
      (node (ref "U$601") (pin "23") (pinfunction "PGND_23") (pintype "power_in"))
      (node (ref "U$601") (pin "4") (pinfunction "PS/SYNC_4") (pintype "input"))
      (node (ref "U$601") (pin "6") (pinfunction "PGND_6") (pintype "power_in"))
      (node (ref "U$601") (pin "7") (pinfunction "PGND_7") (pintype "power_in"))
      (node (ref "U$601") (pin "8") (pinfunction "PGND_8") (pintype "power_in"))
      (node (ref "U$601") (pin "9") (pinfunction "PGND_9") (pintype "power_in"))
      (node (ref "U$601") (pin "EP") (pinfunction "PGND_EP") (pintype "power_in"))
      (node (ref "U$601") (pin "EP1") (pinfunction "PGND_EP1") (pintype "power_in"))
      (node (ref "U$701") (pin "2") (pinfunction "GND_2") (pintype "bidirectional"))
      (node (ref "U$701") (pin "GND") (pinfunction "GND_GND") (pintype "bidirectional"))
      (node (ref "U$702") (pin "2") (pinfunction "GND_2") (pintype "bidirectional"))
      (node (ref "U$702") (pin "4") (pinfunction "EN2_4") (pintype "bidirectional"))
      (node (ref "U$702") (pin "GND") (pinfunction "GND_GND") (pintype "bidirectional"))
      (node (ref "U$703") (pin "2") (pinfunction "VSS_2") (pintype "bidirectional"))
      (node (ref "U$703") (pin "6") (pinfunction "VBAT_6") (pintype "bidirectional"))
      (node (ref "U$703") (pin "GND") (pinfunction "VSS_GND") (pintype "bidirectional"))
      (node (ref "U$703") (pin "P$2") (pinfunction "VSS_P$2") (pintype "bidirectional"))
      (node (ref "U$703") (pin "P$3") (pinfunction "VSS_P$3") (pintype "bidirectional"))
      (node (ref "U$704") (pin "2") (pinfunction "NEG_2") (pintype "bidirectional"))
      (node (ref "U$801") (pin "A") (pinfunction "A_A") (pintype "passive"))
      (node (ref "U101") (pin "10") (pinfunction "VSS_10") (pintype "power_in"))
      (node (ref "U101") (pin "20") (pinfunction "VSSA_20") (pintype "power_in"))
      (node (ref "U101") (pin "27") (pinfunction "VSS_27") (pintype "power_in"))
      (node (ref "U101") (pin "74") (pinfunction "VSS_74") (pintype "power_in"))
      (node (ref "U101") (pin "99") (pinfunction "VSS_99") (pintype "power_in"))
      (node (ref "U401") (pin "2") (pinfunction "GND_2") (pintype "power_in"))
      (node (ref "U401") (pin "5") (pinfunction "SHDN_5") (pintype "input"))
      (node (ref "U401") (pin "8") (pinfunction "RS_8") (pintype "input"))
      (node (ref "U402") (pin "2") (pinfunction "GND_2") (pintype "power_in"))
      (node (ref "U402") (pin "5") (pinfunction "SHDN_5") (pintype "input"))
      (node (ref "U402") (pin "8") (pinfunction "RS_8") (pintype "input"))
      (node (ref "X101") (pin "2") (pinfunction "NC_2_2") (pintype "power_in"))
      (node (ref "X101") (pin "4") (pinfunction "NC_4_4") (pintype "power_in"))
    )
    (net (code "48") (name "GPIO_EXT_1") (class "Default")
      (node (ref "J401") (pin "5") (pinfunction "5_5") (pintype "passive"))
      (node (ref "U101") (pin "8") (pinfunction "PC14_8") (pintype "bidirectional"))
    )
    (net (code "49") (name "GYRO_DRDY") (class "Default")
      (node (ref "U$501") (pin "9") (pinfunction "INT2_9") (pintype "bidirectional"))
      (node (ref "U101") (pin "35") (pinfunction "PB0_35") (pintype "bidirectional"))
    )
    (net (code "50") (name "IO-~{RESET}") (class "Default")
      (node (ref "U$702") (pin "3") (pinfunction "POR2_3") (pintype "bidirectional"))
    )
    (net (code "51") (name "MAG_DRDY") (class "Default")
      (node (ref "U$501") (pin "12") (pinfunction "DSYNC_12") (pintype "bidirectional"))
      (node (ref "U101") (pin "36") (pinfunction "PB1_36") (pintype "bidirectional"))
    )
    (net (code "52") (name "Net-(C101-1)") (class "Default")
      (node (ref "C101") (pin "P$1") (pinfunction "1_P$1") (pintype "passive"))
      (node (ref "U101") (pin "12") (pinfunction "OSC_IN_12") (pintype "input"))
      (node (ref "X101") (pin "3") (pinfunction "3_3") (pintype "bidirectional"))
    )
    (net (code "53") (name "Net-(C102-2)") (class "Default")
      (node (ref "C102") (pin "P$2") (pinfunction "2_P$2") (pintype "passive"))
      (node (ref "U101") (pin "13") (pinfunction "OSC_OUT_13") (pintype "output"))
      (node (ref "X101") (pin "1") (pinfunction "1_1") (pintype "bidirectional"))
    )
    (net (code "54") (name "Net-(C403-1)") (class "Default")
      (node (ref "C403") (pin "P$1") (pinfunction "1_P$1") (pintype "passive"))
      (node (ref "JP403") (pin "2") (pinfunction "2_2") (pintype "passive"))
      (node (ref "R405") (pin "P$2") (pinfunction "2_P$2") (pintype "passive"))
    )
    (net (code "55") (name "Net-(C404-1)") (class "Default")
      (node (ref "C404") (pin "P$1") (pinfunction "1_P$1") (pintype "passive"))
      (node (ref "JP403") (pin "1") (pinfunction "1_1") (pintype "passive"))
      (node (ref "R406") (pin "P$2") (pinfunction "2_P$2") (pintype "passive"))
    )
    (net (code "56") (name "Net-(C503-1)") (class "Default")
      (node (ref "C503") (pin "P$1") (pinfunction "1_P$1") (pintype "passive"))
      (node (ref "U$501") (pin "13") (pinfunction "REGD_13") (pintype "power_in"))
    )
    (net (code "57") (name "Net-(C603-1)") (class "Default")
      (node (ref "C603") (pin "P$1") (pinfunction "1_P$1") (pintype "passive"))
      (node (ref "U$601") (pin "10") (pinfunction "VAUX_10") (pintype "input"))
    )
    (net (code "58") (name "Net-(C703-2)") (class "Default")
      (node (ref "C703") (pin "P$2") (pinfunction "2_P$2") (pintype "passive"))
      (node (ref "U$701") (pin "6") (pinfunction "CSET_6") (pintype "bidirectional"))
    )
    (net (code "59") (name "Net-(C704-1)") (class "Default")
      (node (ref "C704") (pin "P$1") (pinfunction "1_P$1") (pintype "passive"))
      (node (ref "U$702") (pin "6") (pinfunction "CSET_6") (pintype "bidirectional"))
    )
    (net (code "60") (name "Net-(C715-1)") (class "Default")
      (node (ref "C715") (pin "P$1") (pinfunction "1_P$1") (pintype "passive"))
      (node (ref "U101") (pin "49") (pinfunction "VCAP_1_49") (pintype "power_in"))
    )
    (net (code "61") (name "Net-(C717-1)") (class "Default")
      (node (ref "C717") (pin "P$1") (pinfunction "1_P$1") (pintype "passive"))
      (node (ref "U101") (pin "73") (pinfunction "VCAP_2_73") (pintype "power_in"))
    )
    (net (code "62") (name "Net-(J401-Pad8)") (class "Default")
      (node (ref "J401") (pin "8") (pinfunction "8_8") (pintype "passive"))
      (node (ref "L401") (pin "P$2") (pinfunction "P$2_P$2") (pintype "bidirectional"))
    )
    (net (code "63") (name "Net-(J1001A-S)") (class "Default")
      (node (ref "J1001") (pin "S1") (pinfunction "S_S1") (pintype "passive"))
      (node (ref "L1001") (pin "P$9") (pinfunction "P$2_P$9") (pintype "bidirectional"))
    )
    (net (code "64") (name "Net-(J1001B-S)") (class "Default")
      (node (ref "J1001") (pin "S2") (pinfunction "S_S2") (pintype "passive"))
      (node (ref "L1001") (pin "P$10") (pinfunction "P$2_P$10") (pintype "bidirectional"))
    )
    (net (code "65") (name "Net-(J1001C-S)") (class "Default")
      (node (ref "J1001") (pin "S3") (pinfunction "S_S3") (pintype "passive"))
      (node (ref "L1001") (pin "P$12") (pinfunction "P$2_P$12") (pintype "bidirectional"))
    )
    (net (code "66") (name "Net-(J1001D-S)") (class "Default")
      (node (ref "J1001") (pin "S4") (pinfunction "S_S4") (pintype "passive"))
      (node (ref "L1001") (pin "P$11") (pinfunction "P$2_P$11") (pintype "bidirectional"))
    )
    (net (code "67") (name "Net-(J1001E-S)") (class "Default")
      (node (ref "J1001") (pin "S5") (pinfunction "S_S5") (pintype "passive"))
      (node (ref "L1001") (pin "P$13") (pinfunction "P$2_P$13") (pintype "bidirectional"))
    )
    (net (code "68") (name "Net-(J1001F-S)") (class "Default")
      (node (ref "J1001") (pin "S6") (pinfunction "S_S6") (pintype "passive"))
      (node (ref "L1001") (pin "P$14") (pinfunction "P$2_P$14") (pintype "bidirectional"))
    )
    (net (code "69") (name "Net-(J1001G-S)") (class "Default")
      (node (ref "J1001") (pin "S7") (pinfunction "S_S7") (pintype "passive"))
      (node (ref "L1001") (pin "P$15") (pinfunction "P$2_P$15") (pintype "bidirectional"))
    )
    (net (code "70") (name "Net-(J1001H-S)") (class "Default")
      (node (ref "J1001") (pin "S8") (pinfunction "S_S8") (pintype "passive"))
      (node (ref "L1001") (pin "P$16") (pinfunction "P$2_P$16") (pintype "bidirectional"))
    )
    (net (code "71") (name "Net-(JP201-Pad2)") (class "Default")
      (node (ref "JP201") (pin "2") (pinfunction "2_2") (pintype "passive"))
      (node (ref "JP202") (pin "2") (pinfunction "2_2") (pintype "bidirectional"))
      (node (ref "U$201") (pin "C") (pinfunction "C_C") (pintype "passive"))
    )
    (net (code "72") (name "Net-(JP203-Pad2)") (class "Default")
      (node (ref "JP203") (pin "2") (pinfunction "2_2") (pintype "bidirectional"))
      (node (ref "JP204") (pin "2") (pinfunction "2_2") (pintype "bidirectional"))
      (node (ref "JP205") (pin "2") (pinfunction "2_2") (pintype "bidirectional"))
      (node (ref "L203") (pin "P$2") (pinfunction "P$2_P$2") (pintype "bidirectional"))
      (node (ref "U$204") (pin "C") (pinfunction "C_C") (pintype "passive"))
    )
    (net (code "73") (name "Net-(JP401-Pad1)") (class "Default")
      (node (ref "JP401") (pin "1") (pinfunction "1_1") (pintype "passive"))
      (node (ref "JP402") (pin "1") (pinfunction "1_1") (pintype "passive"))
      (node (ref "L402") (pin "P$2") (pinfunction "P$2_P$2") (pintype "bidirectional"))
      (node (ref "U$401") (pin "C") (pinfunction "C_C") (pintype "passive"))
    )
    (net (code "74") (name "Net-(JP404-Pad1)") (class "Default")
      (node (ref "JP404") (pin "1") (pinfunction "1_1") (pintype "passive"))
      (node (ref "JP405") (pin "1") (pinfunction "1_1") (pintype "passive"))
      (node (ref "L404") (pin "P$2") (pinfunction "P$2_P$2") (pintype "bidirectional"))
      (node (ref "U$402") (pin "C") (pinfunction "C_C") (pintype "passive"))
    )
    (net (code "75") (name "Net-(JP1001-1)") (class "Default")
      (node (ref "JP1001") (pin "P$1") (pinfunction "1_P$1") (pintype "passive"))
      (node (ref "R1001") (pin "P$1") (pinfunction "1_P$1") (pintype "passive"))
    )
    (net (code "76") (name "Net-(JP1002-1)") (class "Default")
      (node (ref "JP1002") (pin "P$1") (pinfunction "1_P$1") (pintype "passive"))
      (node (ref "R1002") (pin "P$1") (pinfunction "1_P$1") (pintype "passive"))
    )
    (net (code "77") (name "Net-(L403B-P$2)") (class "Default")
      (node (ref "JP402") (pin "2") (pinfunction "2_2") (pintype "passive"))
      (node (ref "L403") (pin "P$15") (pinfunction "P$2_P$15") (pintype "bidirectional"))
    )
    (net (code "78") (name "Net-(L403D-P$2)") (class "Default")
      (node (ref "JP401") (pin "2") (pinfunction "2_2") (pintype "passive"))
      (node (ref "L403") (pin "P$13") (pinfunction "P$2_P$13") (pintype "bidirectional"))
    )
    (net (code "79") (name "Net-(L403G-P$2)") (class "Default")
      (node (ref "JP402") (pin "3") (pinfunction "3_3") (pintype "passive"))
      (node (ref "L403") (pin "P$10") (pinfunction "P$2_P$10") (pintype "bidirectional"))
    )
    (net (code "80") (name "Net-(L403H-P$2)") (class "Default")
      (node (ref "JP401") (pin "3") (pinfunction "3_3") (pintype "passive"))
      (node (ref "L403") (pin "P$9") (pinfunction "P$2_P$9") (pintype "bidirectional"))
    )
    (net (code "81") (name "Net-(R101-1)") (class "Default")
      (node (ref "R101") (pin "P$1") (pinfunction "1_P$1") (pintype "passive"))
      (node (ref "U101") (pin "37") (pinfunction "PB2_37") (pintype "bidirectional"))
    )
    (net (code "82") (name "Net-(R201-2)") (class "Default")
      (node (ref "JP202") (pin "1") (pinfunction "1_1") (pintype "bidirectional"))
      (node (ref "R201") (pin "P$2") (pinfunction "2_P$2") (pintype "passive"))
      (node (ref "R202") (pin "P$2") (pinfunction "2_P$2") (pintype "passive"))
      (node (ref "U$202") (pin "C") (pinfunction "C_C") (pintype "passive"))
    )
    (net (code "83") (name "Net-(R407-2)") (class "Default")
      (node (ref "R407") (pin "P$2") (pinfunction "2_P$2") (pintype "passive"))
      (node (ref "SJ402") (pin "1") (pinfunction "1_1") (pintype "passive"))
    )
    (net (code "84") (name "Net-(R408-1)") (class "Default")
      (node (ref "R408") (pin "P$1") (pinfunction "1_P$1") (pintype "passive"))
      (node (ref "SJ401") (pin "2") (pinfunction "2_2") (pintype "passive"))
    )
    (net (code "85") (name "Net-(R408-2)") (class "Default")
      (node (ref "JP404") (pin "3") (pinfunction "3_3") (pintype "passive"))
      (node (ref "R408") (pin "P$2") (pinfunction "2_P$2") (pintype "passive"))
      (node (ref "U401") (pin "6") (pinfunction "CANL_6") (pintype "bidirectional"))
    )
    (net (code "86") (name "Net-(R703-1)") (class "Default")
      (node (ref "R703") (pin "P$1") (pinfunction "1_P$1") (pintype "passive"))
      (node (ref "U$703") (pin "7") (pinfunction "ILIM_7") (pintype "bidirectional"))
    )
    (net (code "87") (name "Net-(R706-2)") (class "Default")
      (node (ref "D701") (pin "C") (pinfunction "C_C") (pintype "passive"))
      (node (ref "R706") (pin "P$2") (pinfunction "2_P$2") (pintype "passive"))
    )
    (net (code "88") (name "Net-(R801-1)") (class "Default")
      (node (ref "JP801") (pin "2") (pinfunction "2_2") (pintype "passive"))
      (node (ref "R801") (pin "P$1") (pinfunction "1_P$1") (pintype "passive"))
    )
    (net (code "89") (name "Net-(R803-1)") (class "Default")
      (node (ref "R803") (pin "P$1") (pinfunction "1_P$1") (pintype "passive"))
      (node (ref "R804") (pin "P$2") (pinfunction "2_P$2") (pintype "passive"))
    )
    (net (code "90") (name "Net-(R803-2)") (class "Default")
      (node (ref "LED801") (pin "C") (pinfunction "C_C") (pintype "passive"))
      (node (ref "R803") (pin "P$2") (pinfunction "2_P$2") (pintype "passive"))
    )
    (net (code "91") (name "Net-(R805-2)") (class "Default")
      (node (ref "LED802") (pin "C") (pinfunction "C_C") (pintype "passive"))
      (node (ref "R805") (pin "P$2") (pinfunction "2_P$2") (pintype "passive"))
    )
    (net (code "92") (name "Net-(R901-1)") (class "Default")
      (node (ref "D901") (pin "C") (pinfunction "C_C") (pintype "passive"))
      (node (ref "R901") (pin "P$1") (pinfunction "1_P$1") (pintype "passive"))
      (node (ref "R902") (pin "P$2") (pinfunction "2_P$2") (pintype "passive"))
    )
    (net (code "93") (name "Net-(U$301-D1I)") (class "Default")
      (node (ref "JP301") (pin "2") (pinfunction "2_2") (pintype "passive"))
      (node (ref "U$301") (pin "1") (pinfunction "D1I_1") (pintype "bidirectional"))
    )
    (net (code "94") (name "Net-(U$301-D2I)") (class "Default")
      (node (ref "JP301") (pin "3") (pinfunction "3_3") (pintype "passive"))
      (node (ref "U$301") (pin "3") (pinfunction "D2I_3") (pintype "bidirectional"))
    )
    (net (code "95") (name "Net-(U$601-L1)") (class "Default")
      (node (ref "L$601") (pin "2") (pinfunction "2_2") (pintype "passive"))
      (node (ref "U$601") (pin "1") (pinfunction "L1_1") (pintype "bidirectional"))
    )
    (net (code "96") (name "Net-(U$601-L2)") (class "Default")
      (node (ref "L$601") (pin "1") (pinfunction "1_1") (pintype "passive"))
      (node (ref "U$601") (pin "14") (pinfunction "L2_14") (pintype "bidirectional"))
    )
    (net (code "97") (name "Net-(U401-CANH)") (class "Default")
      (node (ref "JP404") (pin "2") (pinfunction "2_2") (pintype "passive"))
      (node (ref "SJ401") (pin "1") (pinfunction "1_1") (pintype "passive"))
      (node (ref "U401") (pin "7") (pinfunction "CANH_7") (pintype "bidirectional"))
    )
    (net (code "98") (name "OTG_FS_DM") (class "Default")
      (node (ref "U$301") (pin "6") (pinfunction "D1O_6") (pintype "bidirectional"))
      (node (ref "U101") (pin "70") (pinfunction "PA11_70") (pintype "bidirectional"))
    )
    (net (code "99") (name "OTG_FS_DP") (class "Default")
      (node (ref "U$301") (pin "4") (pinfunction "D2O_4") (pintype "bidirectional"))
      (node (ref "U101") (pin "71") (pinfunction "PA12_71") (pintype "bidirectional"))
    )
    (net (code "100") (name "PPM_INPUT") (class "Default")
      (node (ref "R201") (pin "P$1") (pinfunction "1_P$1") (pintype "passive"))
      (node (ref "R203") (pin "P$1") (pinfunction "1_P$1") (pintype "passive"))
      (node (ref "U$203") (pin "2") (pinfunction "1A_2") (pintype "bidirectional"))
      (node (ref "U101") (pin "23") (pinfunction "PA0_23") (pintype "bidirectional"))
    )
    (net (code "101") (name "SAFETY") (class "Default")
      (node (ref "JP801") (pin "3") (pinfunction "3_3") (pintype "passive"))
      (node (ref "R802") (pin "P$1") (pinfunction "1_P$1") (pintype "passive"))
      (node (ref "U101") (pin "93") (pinfunction "PB7_93") (pintype "bidirectional"))
    )
    (net (code "102") (name "SBUS_OUTPUT_ENABLE") (class "Default")
      (node (ref "R204") (pin "P$2") (pinfunction "2_P$2") (pintype "passive"))
      (node (ref "U$203") (pin "7") (pinfunction "~{2OE}_7") (pintype "input"))
      (node (ref "U101") (pin "91") (pinfunction "PB5_91") (pintype "bidirectional"))
    )
    (net (code "103") (name "SDIO_CK") (class "Default")
      (node (ref "U$302") (pin "6") (pinfunction "CLK_6") (pintype "bidirectional"))
      (node (ref "U101") (pin "80") (pinfunction "PC12_80") (pintype "bidirectional"))
    )
    (net (code "104") (name "SDIO_CMD") (class "Default")
      (node (ref "U$302") (pin "1") (pinfunction "~{CS}_1") (pintype "bidirectional"))
      (node (ref "U101") (pin "83") (pinfunction "PD2_83") (pintype "bidirectional"))
    )
    (net (code "105") (name "SDIO_D0") (class "Default")
      (node (ref "U$302") (pin "5") (pinfunction "DI/IO0_5") (pintype "bidirectional"))
      (node (ref "U101") (pin "65") (pinfunction "PC8_65") (pintype "bidirectional"))
    )
    (net (code "106") (name "SDIO_D1") (class "Default")
      (node (ref "U$302") (pin "2") (pinfunction "DO/IO1_2") (pintype "bidirectional"))
      (node (ref "U101") (pin "66") (pinfunction "PC9_66") (pintype "bidirectional"))
    )
    (net (code "107") (name "SDIO_D2") (class "Default")
      (node (ref "U$302") (pin "3") (pinfunction "~{WP}/IO2_3") (pintype "bidirectional"))
      (node (ref "U101") (pin "78") (pinfunction "PC10_78") (pintype "bidirectional"))
    )
    (net (code "108") (name "SDIO_D3") (class "Default")
      (node (ref "U$302") (pin "7") (pinfunction "~{HOLD}/IO3_7") (pintype "bidirectional"))
      (node (ref "U101") (pin "79") (pinfunction "PC11_79") (pintype "bidirectional"))
    )
    (net (code "109") (name "SERIAL1_CTS") (class "Default")
      (node (ref "JP203") (pin "6") (pinfunction "6_6") (pintype "bidirectional"))
      (node (ref "L201") (pin "P$16") (pinfunction "P$2_P$16") (pintype "bidirectional"))
    )
    (net (code "110") (name "SERIAL1_RTS") (class "Default")
      (node (ref "JP203") (pin "4") (pinfunction "4_4") (pintype "bidirectional"))
      (node (ref "L201") (pin "P$15") (pinfunction "P$2_P$15") (pintype "bidirectional"))
    )
    (net (code "111") (name "SERIAL1_RX") (class "Default")
      (node (ref "JP203") (pin "3") (pinfunction "3_3") (pintype "bidirectional"))
      (node (ref "L201") (pin "P$13") (pinfunction "P$2_P$13") (pintype "bidirectional"))
    )
    (net (code "112") (name "SERIAL1_TX") (class "Default")
      (node (ref "JP203") (pin "1") (pinfunction "1_1") (pintype "bidirectional"))
      (node (ref "L201") (pin "P$14") (pinfunction "P$2_P$14") (pintype "bidirectional"))
    )
    (net (code "113") (name "SERIAL2_CTS") (class "Default")
      (node (ref "JP204") (pin "6") (pinfunction "6_6") (pintype "bidirectional"))
      (node (ref "L201") (pin "P$10") (pinfunction "P$2_P$10") (pintype "bidirectional"))
    )
    (net (code "114") (name "SERIAL2_RTS") (class "Default")
      (node (ref "JP204") (pin "4") (pinfunction "4_4") (pintype "bidirectional"))
      (node (ref "L201") (pin "P$9") (pinfunction "P$2_P$9") (pintype "bidirectional"))
    )
    (net (code "115") (name "SERIAL2_RX") (class "Default")
      (node (ref "JP204") (pin "3") (pinfunction "3_3") (pintype "bidirectional"))
      (node (ref "L201") (pin "P$11") (pinfunction "P$2_P$11") (pintype "bidirectional"))
    )
    (net (code "116") (name "SERIAL2_TX") (class "Default")
      (node (ref "JP204") (pin "1") (pinfunction "1_1") (pintype "bidirectional"))
      (node (ref "L201") (pin "P$12") (pinfunction "P$2_P$12") (pintype "bidirectional"))
    )
    (net (code "117") (name "SERIAL3_RX") (class "Default")
      (node (ref "JP205") (pin "3") (pinfunction "3_3") (pintype "bidirectional"))
      (node (ref "L202") (pin "P$9") (pinfunction "P$2_P$9") (pintype "bidirectional"))
    )
    (net (code "118") (name "SERIAL3_TX") (class "Default")
      (node (ref "JP205") (pin "1") (pinfunction "1_1") (pintype "bidirectional"))
      (node (ref "L202") (pin "P$11") (pinfunction "P$2_P$11") (pintype "bidirectional"))
    )
    (net (code "119") (name "SPEKTRUM_RX") (class "Default")
      (node (ref "R202") (pin "P$1") (pinfunction "1_P$1") (pintype "passive"))
      (node (ref "U101") (pin "69") (pinfunction "PA10_69") (pintype "bidirectional"))
    )
    (net (code "120") (name "SPI_EXT_MISO") (class "Default")
      (node (ref "J401") (pin "3") (pinfunction "3_3") (pintype "passive"))
      (node (ref "U101") (pin "4") (pinfunction "PE5_4") (pintype "bidirectional"))
    )
    (net (code "121") (name "SPI_EXT_MOSI") (class "Default")
      (node (ref "J401") (pin "6") (pinfunction "6_6") (pintype "passive"))
      (node (ref "U101") (pin "5") (pinfunction "PE6_5") (pintype "bidirectional"))
    )
    (net (code "122") (name "SPI_EXT_SCK") (class "Default")
      (node (ref "J401") (pin "2") (pinfunction "2_2") (pintype "passive"))
      (node (ref "U101") (pin "1") (pinfunction "PE2_1") (pintype "bidirectional"))
    )
    (net (code "123") (name "SPI_INT_MISO") (class "Default")
      (node (ref "U$501") (pin "7") (pinfunction "SA0/MISO_7") (pintype "bidirectional"))
      (node (ref "U101") (pin "31") (pinfunction "PA6_31") (pintype "bidirectional"))
    )
    (net (code "124") (name "SPI_INT_MOSI") (class "Default")
      (node (ref "U$501") (pin "6") (pinfunction "SDA/MOSI_6") (pintype "bidirectional"))
      (node (ref "U101") (pin "32") (pinfunction "PA7_32") (pintype "bidirectional"))
    )
    (net (code "125") (name "SPI_INT_SCK") (class "Default")
      (node (ref "U$501") (pin "4") (pinfunction "SCL/CLK_4") (pintype "bidirectional"))
      (node (ref "U101") (pin "30") (pinfunction "PA5_30") (pintype "bidirectional"))
    )
    (net (code "126") (name "VBAT") (class "Default")
      (node (ref "R706") (pin "P$1") (pinfunction "1_P$1") (pintype "passive"))
      (node (ref "U$704") (pin "1") (pinfunction "POS_1") (pintype "bidirectional"))
      (node (ref "U101") (pin "6") (pinfunction "VBAT_6") (pintype "power_in"))
    )
    (net (code "127") (name "VBUS") (class "Default")
      (node (ref "D904") (pin "ANODE") (pinfunction "A_ANODE") (pintype "passive"))
      (node (ref "JP301") (pin "1") (pinfunction "1_1") (pintype "passive"))
      (node (ref "U$301") (pin "5") (pinfunction "VBUS_5") (pintype "bidirectional"))
      (node (ref "U101") (pin "68") (pinfunction "PA9_68") (pintype "bidirectional"))
    )
    (net (code "128") (name "VDD_3V3_SENSORS") (class "Default")
      (node (ref "C501") (pin "P$1") (pinfunction "1_P$1") (pintype "passive"))
      (node (ref "C502") (pin "P$1") (pinfunction "1_P$1") (pintype "passive"))
      (node (ref "C707") (pin "P$1") (pinfunction "1_P$1") (pintype "passive"))
      (node (ref "U$501") (pin "1") (pinfunction "VDD_IO_1") (pintype "power_in"))
      (node (ref "U$501") (pin "14") (pinfunction "VDD_14") (pintype "power_in"))
      (node (ref "U$501") (pin "15") (pinfunction "RSV2_15") (pintype "input"))
      (node (ref "U$702") (pin "8") (pinfunction "VOUT1_8") (pintype "bidirectional"))
    )
    (net (code "129") (name "VDD_3V3_SENSORS_EN") (class "Default")
      (node (ref "R702") (pin "P$2") (pinfunction "2_P$2") (pintype "passive"))
      (node (ref "U$702") (pin "5") (pinfunction "EN1_5") (pintype "bidirectional"))
      (node (ref "U101") (pin "2") (pinfunction "PE3_2") (pintype "bidirectional"))
    )
    (net (code "130") (name "VDD_3V3_SPEKTRUM") (class "Default")
      (node (ref "C708") (pin "P$1") (pinfunction "1_P$1") (pintype "passive"))
      (node (ref "JP201") (pin "1") (pinfunction "1_1") (pintype "passive"))
      (node (ref "U$701") (pin "8") (pinfunction "VOUT1_8") (pintype "bidirectional"))
    )
    (net (code "131") (name "VDD_3V3_SPEKTRUM_EN") (class "Default")
      (node (ref "R701") (pin "P$2") (pinfunction "2_P$2") (pintype "passive"))
      (node (ref "U$701") (pin "5") (pinfunction "EN1_5") (pintype "bidirectional"))
      (node (ref "U101") (pin "17") (pinfunction "PC2_17") (pintype "bidirectional"))
    )
    (net (code "132") (name "VDD_5V") (class "Default")
      (node (ref "C604") (pin "1") (pinfunction "1_1") (pintype "passive"))
      (node (ref "C605") (pin "1") (pinfunction "1_1") (pintype "passive"))
      (node (ref "C606") (pin "1") (pinfunction "1_1") (pintype "passive"))
      (node (ref "C701") (pin "P$1") (pinfunction "1_P$1") (pintype "passive"))
      (node (ref "C702") (pin "P$1") (pinfunction "1_P$1") (pintype "passive"))
      (node (ref "LED801") (pin "A") (pinfunction "A_A") (pintype "passive"))
      (node (ref "LED802") (pin "A") (pinfunction "A_A") (pintype "passive"))
      (node (ref "R707") (pin "P$2") (pinfunction "2_P$2") (pintype "passive"))
      (node (ref "U$601") (pin "13") (pinfunction "VOUT_13") (pintype "power_in"))
      (node (ref "U$701") (pin "1") (pinfunction "VIN_1") (pintype "bidirectional"))
      (node (ref "U$701") (pin "4") (pinfunction "EN2_4") (pintype "bidirectional"))
      (node (ref "U$702") (pin "1") (pinfunction "VIN_1") (pintype "bidirectional"))
      (node (ref "U$703") (pin "1") (pinfunction "IN_1") (pintype "bidirectional"))
    )
    (net (code "133") (name "VDD_5V_PERIPH") (class "Default")
      (node (ref "JP201") (pin "3") (pinfunction "3_3") (pintype "passive"))
      (node (ref "L203") (pin "P$1") (pinfunction "P$1_P$1") (pintype "bidirectional"))
      (node (ref "L401") (pin "P$1") (pinfunction "P$1_P$1") (pintype "bidirectional"))
      (node (ref "L402") (pin "P$1") (pinfunction "P$1_P$1") (pintype "bidirectional"))
      (node (ref "L404") (pin "P$1") (pinfunction "P$1_P$1") (pintype "bidirectional"))
      (node (ref "U$703") (pin "8") (pinfunction "OUT_8") (pintype "bidirectional"))
    )
    (net (code "134") (name "VDD_5V_SENS") (class "Default")
      (node (ref "R707") (pin "P$1") (pinfunction "1_P$1") (pintype "passive"))
      (node (ref "R708") (pin "P$1") (pinfunction "1_P$1") (pintype "passive"))
      (node (ref "U101") (pin "29") (pinfunction "PA4_29") (pintype "bidirectional"))
    )
    (net (code "135") (name "VDD_IN") (class "Default")
      (node (ref "C601") (pin "1") (pinfunction "1_1") (pintype "passive"))
      (node (ref "C602") (pin "P$1") (pinfunction "1_P$1") (pintype "passive"))
      (node (ref "D902") (pin "C") (pinfunction "C_C") (pintype "passive"))
      (node (ref "D903") (pin "C") (pinfunction "C_C") (pintype "passive"))
      (node (ref "D904") (pin "CATHODE") (pinfunction "C_CATHODE") (pintype "passive"))
      (node (ref "U$601") (pin "2") (pinfunction "VIN_2") (pintype "power_in"))
      (node (ref "U$601") (pin "3") (pinfunction "EN_3") (pintype "input"))
    )
    (net (code "136") (name "VDD_SERVO_SENSE") (class "Default")
      (node (ref "R902") (pin "P$1") (pinfunction "1_P$1") (pintype "passive"))
      (node (ref "R903") (pin "P$2") (pinfunction "2_P$2") (pintype "passive"))
      (node (ref "U101") (pin "16") (pinfunction "PC1_16") (pintype "bidirectional"))
    )
    (net (code "137") (name "V_EXT") (class "Default")
      (node (ref "D903") (pin "A") (pinfunction "A_A") (pintype "passive"))
      (node (ref "JP901") (pin "1") (pinfunction "1_1") (pintype "passive"))
      (node (ref "R901") (pin "P$2") (pinfunction "2_P$2") (pintype "passive"))
    )
    (net (code "138") (name "V_SERVO") (class "Default")
      (node (ref "D902") (pin "A") (pinfunction "A_A") (pintype "passive"))
      (node (ref "J1001") (pin "PWR_S1") (pinfunction "S_PWR_S1") (pintype "passive"))
      (node (ref "J1001") (pin "PWR_S2") (pinfunction "S_PWR_S2") (pintype "passive"))
      (node (ref "J1001") (pin "PWR_S3") (pinfunction "S_PWR_S3") (pintype "passive"))
      (node (ref "J1001") (pin "PWR_S4") (pinfunction "S_PWR_S4") (pintype "passive"))
      (node (ref "J1001") (pin "PWR_S5") (pinfunction "S_PWR_S5") (pintype "passive"))
      (node (ref "J1001") (pin "PWR_S6") (pinfunction "S_PWR_S6") (pintype "passive"))
      (node (ref "J1001") (pin "PWR_S7") (pinfunction "S_PWR_S7") (pintype "passive"))
      (node (ref "J1001") (pin "PWR_S8") (pinfunction "S_PWR_S8") (pintype "passive"))
    )
    (net (code "139") (name "unconnected-(J401-Pad1)") (class "Default")
      (node (ref "J401") (pin "1") (pinfunction "1_1") (pintype "passive"))
    )
    (net (code "140") (name "unconnected-(JP205-Pad4)") (class "Default")
      (node (ref "JP205") (pin "4") (pinfunction "4_4") (pintype "bidirectional"))
    )
    (net (code "141") (name "unconnected-(JP205-Pad6)") (class "Default")
      (node (ref "JP205") (pin "6") (pinfunction "6_6") (pintype "bidirectional"))
    )
    (net (code "142") (name "unconnected-(JX301F-S-Pad8)") (class "Default")
      (node (ref "JX301") (pin "8") (pinfunction "S_8") (pintype "passive"))
    )
    (net (code "143") (name "unconnected-(L202-PadP$1)") (class "Default")
      (node (ref "L202") (pin "P$1") (pinfunction "P$1_P$1") (pintype "bidirectional"))
    )
    (net (code "144") (name "unconnected-(L202A-P$2-PadP$16)") (class "Default")
      (node (ref "L202") (pin "P$16") (pinfunction "P$2_P$16") (pintype "bidirectional"))
    )
    (net (code "145") (name "unconnected-(L202B-P$1-PadP$2)") (class "Default")
      (node (ref "L202") (pin "P$2") (pinfunction "P$1_P$2") (pintype "bidirectional"))
    )
    (net (code "146") (name "unconnected-(L202B-P$2-PadP$15)") (class "Default")
      (node (ref "L202") (pin "P$15") (pinfunction "P$2_P$15") (pintype "bidirectional"))
    )
    (net (code "147") (name "unconnected-(L202C-P$1-PadP$3)") (class "Default")
      (node (ref "L202") (pin "P$3") (pinfunction "P$1_P$3") (pintype "bidirectional"))
    )
    (net (code "148") (name "unconnected-(L202C-P$2-PadP$14)") (class "Default")
      (node (ref "L202") (pin "P$14") (pinfunction "P$2_P$14") (pintype "bidirectional"))
    )
    (net (code "149") (name "unconnected-(L202D-P$1-PadP$4)") (class "Default")
      (node (ref "L202") (pin "P$4") (pinfunction "P$1_P$4") (pintype "bidirectional"))
    )
    (net (code "150") (name "unconnected-(L202D-P$2-PadP$13)") (class "Default")
      (node (ref "L202") (pin "P$13") (pinfunction "P$2_P$13") (pintype "bidirectional"))
    )
    (net (code "151") (name "unconnected-(L202E-P$1-PadP$5)") (class "Default")
      (node (ref "L202") (pin "P$5") (pinfunction "P$1_P$5") (pintype "bidirectional"))
    )
    (net (code "152") (name "unconnected-(L202E-P$2-PadP$12)") (class "Default")
      (node (ref "L202") (pin "P$12") (pinfunction "P$2_P$12") (pintype "bidirectional"))
    )
    (net (code "153") (name "unconnected-(L202G-P$1-PadP$7)") (class "Default")
      (node (ref "L202") (pin "P$7") (pinfunction "P$1_P$7") (pintype "bidirectional"))
    )
    (net (code "154") (name "unconnected-(L202G-P$2-PadP$10)") (class "Default")
      (node (ref "L202") (pin "P$10") (pinfunction "P$2_P$10") (pintype "bidirectional"))
    )
    (net (code "155") (name "unconnected-(L403-PadP$1)") (class "Default")
      (node (ref "L403") (pin "P$1") (pinfunction "P$1_P$1") (pintype "bidirectional"))
    )
    (net (code "156") (name "unconnected-(L403A-P$2-PadP$16)") (class "Default")
      (node (ref "L403") (pin "P$16") (pinfunction "P$2_P$16") (pintype "bidirectional"))
    )
    (net (code "157") (name "unconnected-(L403C-P$1-PadP$3)") (class "Default")
      (node (ref "L403") (pin "P$3") (pinfunction "P$1_P$3") (pintype "bidirectional"))
    )
    (net (code "158") (name "unconnected-(L403C-P$2-PadP$14)") (class "Default")
      (node (ref "L403") (pin "P$14") (pinfunction "P$2_P$14") (pintype "bidirectional"))
    )
    (net (code "159") (name "unconnected-(L403E-P$1-PadP$5)") (class "Default")
      (node (ref "L403") (pin "P$5") (pinfunction "P$1_P$5") (pintype "bidirectional"))
    )
    (net (code "160") (name "unconnected-(L403E-P$2-PadP$12)") (class "Default")
      (node (ref "L403") (pin "P$12") (pinfunction "P$2_P$12") (pintype "bidirectional"))
    )
    (net (code "161") (name "unconnected-(L403F-P$1-PadP$6)") (class "Default")
      (node (ref "L403") (pin "P$6") (pinfunction "P$1_P$6") (pintype "bidirectional"))
    )
    (net (code "162") (name "unconnected-(L403F-P$2-PadP$11)") (class "Default")
      (node (ref "L403") (pin "P$11") (pinfunction "P$2_P$11") (pintype "bidirectional"))
    )
    (net (code "163") (name "unconnected-(U$501-MST_SCL-Pad2)") (class "Default")
      (node (ref "U$501") (pin "2") (pinfunction "MST_SCL_2") (pintype "bidirectional"))
    )
    (net (code "164") (name "unconnected-(U$501-MST_SDA-Pad3)") (class "Default")
      (node (ref "U$501") (pin "3") (pinfunction "MST_SDA_3") (pintype "bidirectional"))
    )
    (net (code "165") (name "unconnected-(U$501-RSV3-Pad16)") (class "Default")
      (node (ref "U$501") (pin "16") (pinfunction "RSV3_16") (pintype "no_connect"))
    )
    (net (code "166") (name "unconnected-(U$601-FB-Pad12)") (class "Default")
      (node (ref "U$601") (pin "12") (pinfunction "FB_12") (pintype "input"))
    )
    (net (code "167") (name "unconnected-(U$601-PG-Pad5)") (class "Default")
      (node (ref "U$601") (pin "5") (pinfunction "PG_5") (pintype "output"))
    )
    (net (code "168") (name "unconnected-(U$702-VOUT2-Pad7)") (class "Default")
      (node (ref "U$702") (pin "7") (pinfunction "VOUT2_7") (pintype "bidirectional"))
    )
    (net (code "169") (name "unconnected-(U101I-PC0-Pad15)") (class "Default")
      (node (ref "U101") (pin "15") (pinfunction "PC0_15") (pintype "bidirectional"))
    )
    (net (code "170") (name "unconnected-(U101I-PC5-Pad34)") (class "Default")
      (node (ref "U101") (pin "34") (pinfunction "PC5_34") (pintype "bidirectional"))
    )
    (net (code "171") (name "unconnected-(U101I-PC6-Pad63)") (class "Default")
      (node (ref "U101") (pin "63") (pinfunction "PC6_63") (pintype "bidirectional"))
    )
    (net (code "172") (name "unconnected-(U101I-PC7-Pad64)") (class "Default")
      (node (ref "U101") (pin "64") (pinfunction "PC7_64") (pintype "bidirectional"))
    )
    (net (code "173") (name "unconnected-(U101L-PE10-Pad41)") (class "Default")
      (node (ref "U101") (pin "41") (pinfunction "PE10_41") (pintype "bidirectional"))
    )
    (net (code "174") (name "~{BARO_CS}") (class "Default")
      (node (ref "U101") (pin "88") (pinfunction "PD7_88") (pintype "bidirectional"))
    )
    (net (code "175") (name "~{FMU-LED_AMBER}") (class "Default")
      (node (ref "R804") (pin "P$1") (pinfunction "1_P$1") (pintype "passive"))
      (node (ref "U101") (pin "43") (pinfunction "PE12_43") (pintype "bidirectional"))
    )
    (net (code "176") (name "~{FRAM_CS}") (class "Default")
      (node (ref "U101") (pin "57") (pinfunction "PD10_57") (pintype "bidirectional"))
    )
    (net (code "177") (name "~{GYRO_CS}") (class "Default")
      (node (ref "U$501") (pin "8") (pinfunction "CS_8") (pintype "bidirectional"))
      (node (ref "U101") (pin "7") (pinfunction "PC13_7") (pintype "bidirectional"))
    )
    (net (code "178") (name "~{SPI_EXT_NSS}") (class "Default")
      (node (ref "J401") (pin "4") (pinfunction "4_4") (pintype "passive"))
      (node (ref "U101") (pin "3") (pinfunction "PE4_3") (pintype "bidirectional"))
    )
    (net (code "179") (name "~{VDD_5V_PERIPH_EN}") (class "Default")
      (node (ref "R704") (pin "P$2") (pinfunction "2_P$2") (pintype "passive"))
      (node (ref "U$703") (pin "5") (pinfunction "~{CE}_5") (pintype "bidirectional"))
      (node (ref "U101") (pin "67") (pinfunction "PA8_67") (pintype "bidirectional"))
    )
    (net (code "180") (name "~{VDD_5V_PERIPH_OC}") (class "Default")
      (node (ref "R705") (pin "P$2") (pinfunction "2_P$2") (pintype "passive"))
      (node (ref "U$703") (pin "4") (pinfunction "~{FAULT}_4") (pintype "bidirectional"))
      (node (ref "U101") (pin "46") (pinfunction "PE15_46") (pintype "bidirectional"))
    )
  )
)
